# SI5324_CDR_WR_oscillators.net
KiCad netlist of a schematic drawn in Altium Designer
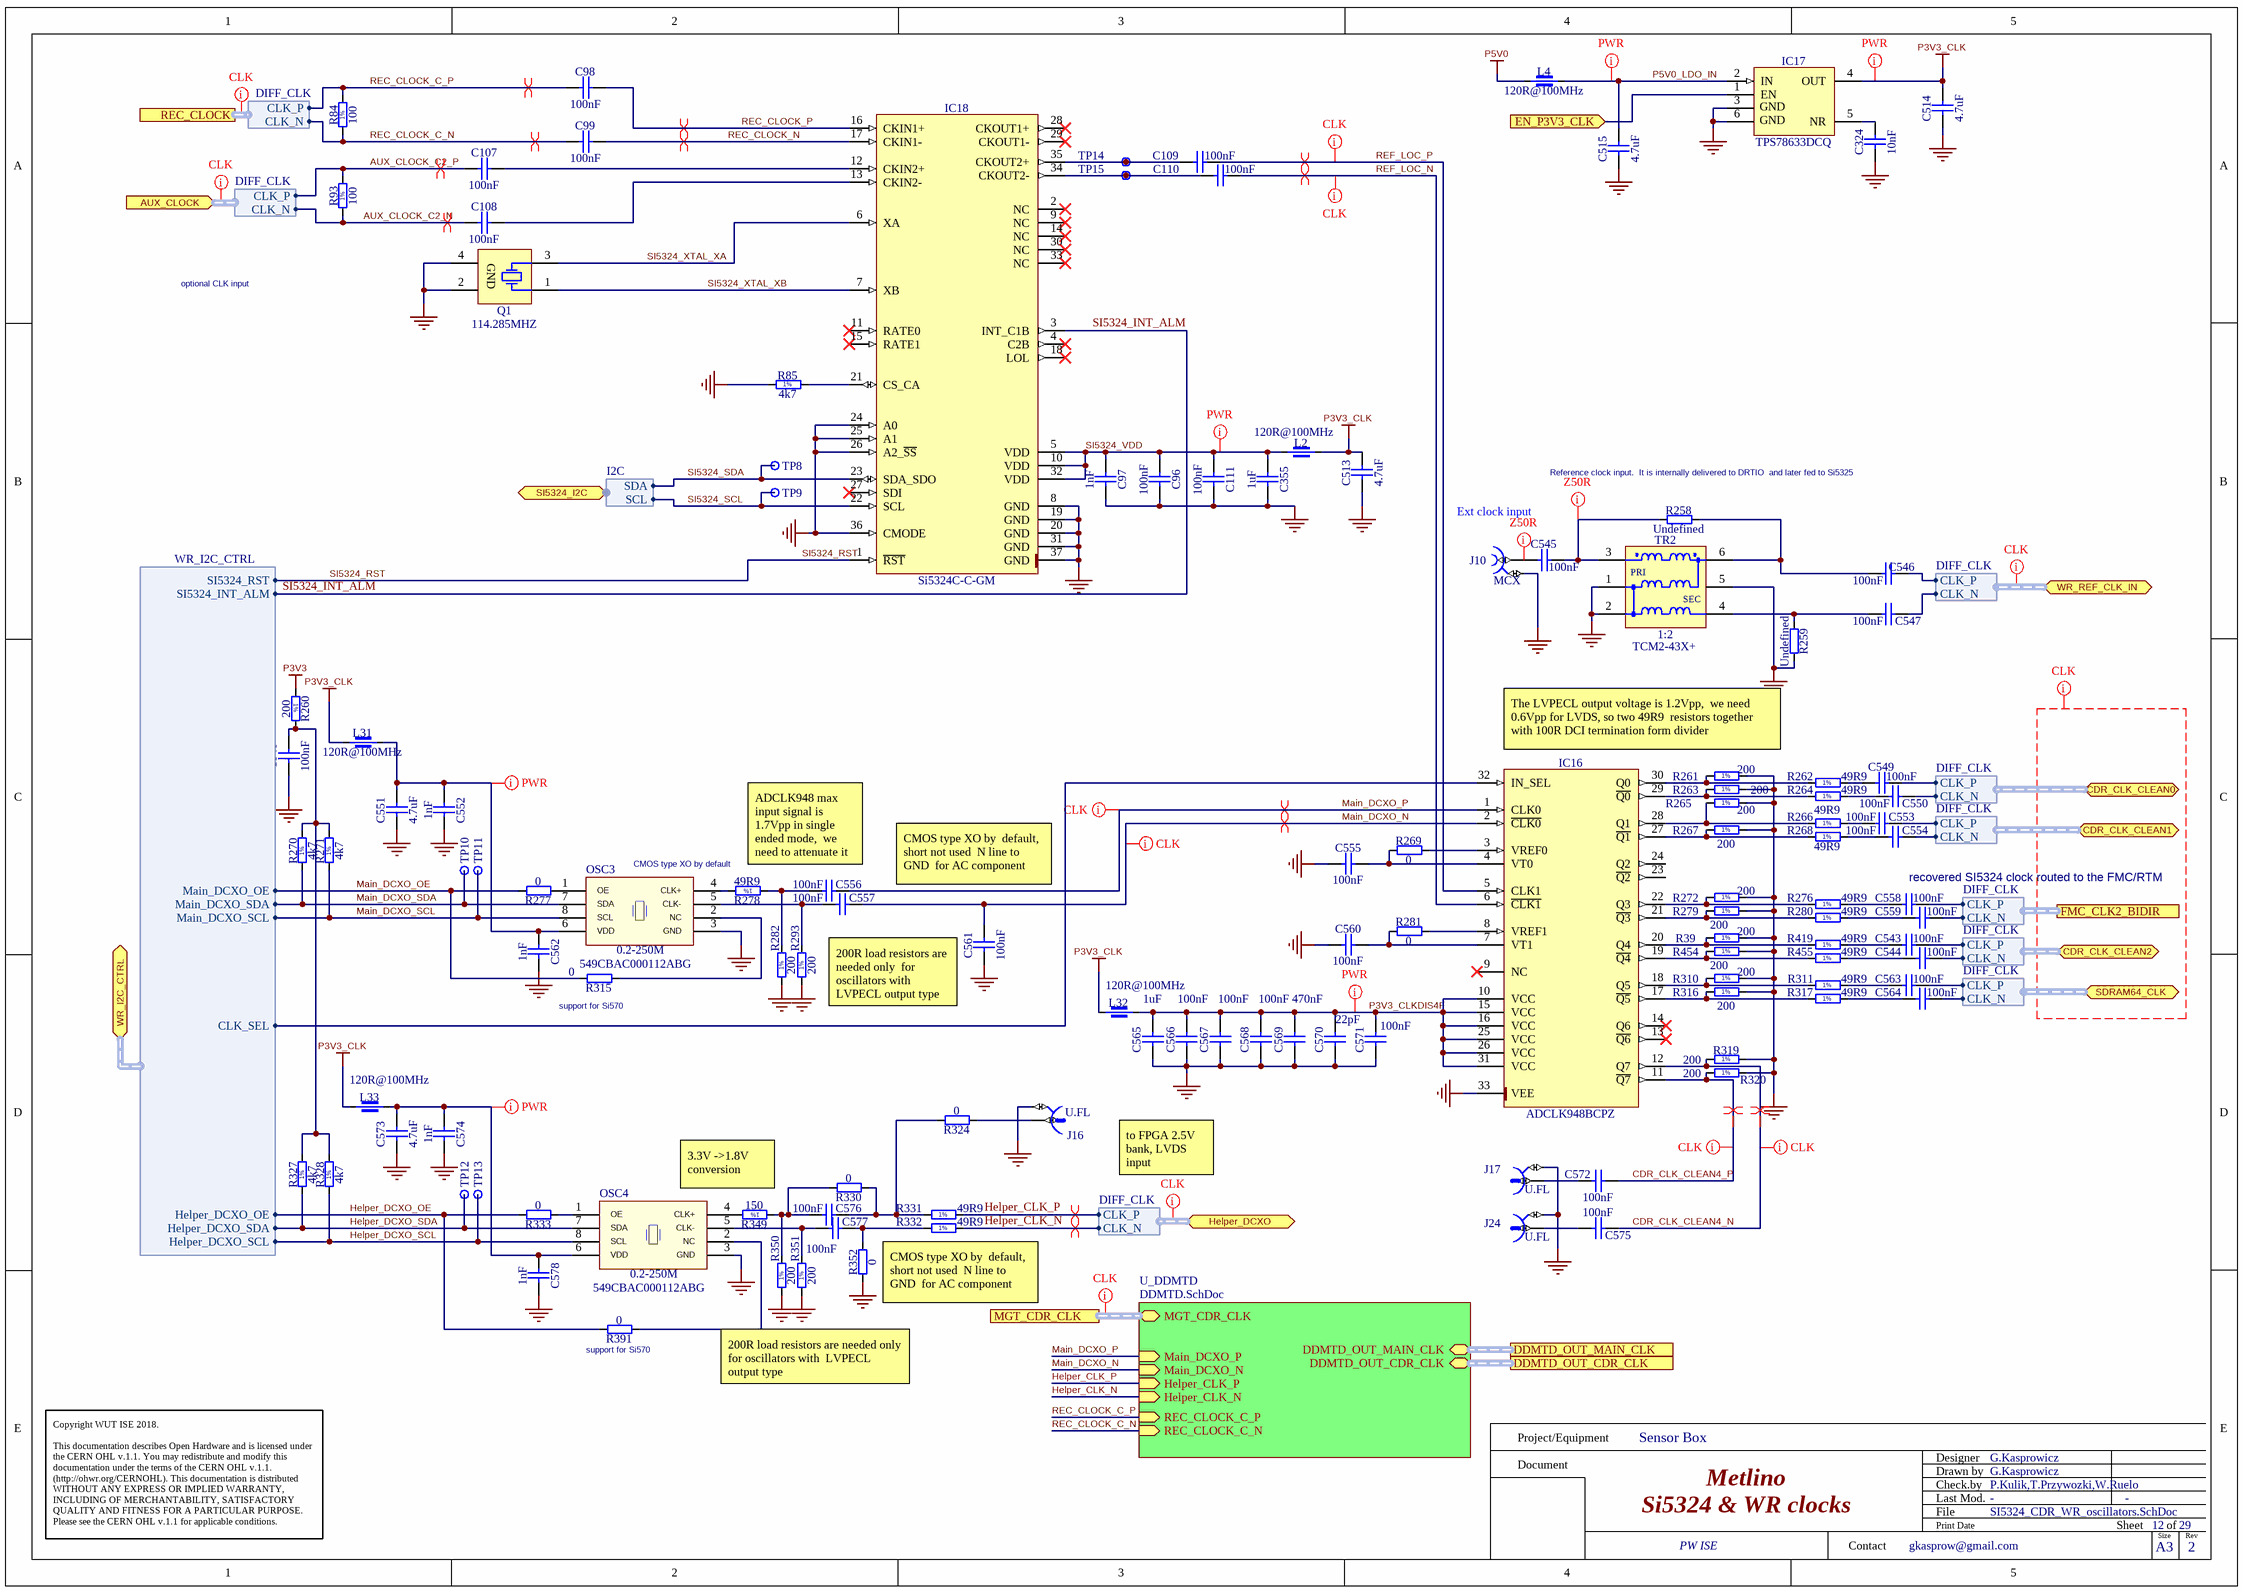
[diagram p0: SI5324_CDR_WR_oscillators.SchDoc]

(export (version "E")
  (design (tool "Eeschema 10.0.6"))
  (components
    (comp (ref "C96")
      (value "100nF")
      (footprint "CAPC0603X33N")
      (description "Non-polarised capacitor")
      (fields
        (field (name "MANUFACTURER PART NUMBER") "CC0201_100NF_6.3V_10%_X5R")
        (field (name "MANUFACTURER") "GENERIC")
        (field (name "AUTHOR") "CERN DEM JLC")
      )
      (libsource (lib "Capacitors") (part "Capacitor - non polarized"))
    )
    (comp (ref "C97")
      (value "1nF")
      (footprint "CAPC0603X33N")
      (description "Non-polarised capacitor")
      (fields
        (field (name "MANUFACTURER PART NUMBER") "CC0201_1NF_16V_10%_X5R")
        (field (name "MANUFACTURER") "GENERIC")
        (field (name "AUTHOR") "CERN DEM JLC")
      )
      (libsource (lib "Capacitors") (part "Capacitor - non polarized"))
    )
    (comp (ref "C98")
      (value "100nF")
      (footprint "CAPC0603X33N")
      (description "Non-polarised capacitor")
      (fields
        (field (name "MANUFACTURER PART NUMBER") "CC0201_100NF_6.3V_10%_X5R")
        (field (name "MANUFACTURER") "GENERIC")
        (field (name "AUTHOR") "CERN DEM JLC")
      )
      (libsource (lib "Capacitors") (part "Capacitor - non polarized"))
    )
    (comp (ref "C99")
      (value "100nF")
      (footprint "CAPC0603X33N")
      (description "Non-polarised capacitor")
      (fields
        (field (name "MANUFACTURER PART NUMBER") "CC0201_100NF_6.3V_10%_X5R")
        (field (name "MANUFACTURER") "GENERIC")
        (field (name "AUTHOR") "CERN DEM JLC")
      )
      (libsource (lib "Capacitors") (part "Capacitor - non polarized"))
    )
    (comp (ref "C107")
      (value "100nF")
      (footprint "CAPC0603X33N")
      (description "Non-polarised capacitor")
      (fields
        (field (name "MANUFACTURER PART NUMBER") "CC0201_100NF_6.3V_10%_X5R")
        (field (name "MANUFACTURER") "GENERIC")
        (field (name "AUTHOR") "CERN DEM JLC")
      )
      (libsource (lib "Capacitors") (part "Capacitor - non polarized"))
    )
    (comp (ref "C108")
      (value "100nF")
      (footprint "CAPC0603X33N")
      (description "Non-polarised capacitor")
      (fields
        (field (name "MANUFACTURER PART NUMBER") "CC0201_100NF_6.3V_10%_X5R")
        (field (name "MANUFACTURER") "GENERIC")
        (field (name "AUTHOR") "CERN DEM JLC")
      )
      (libsource (lib "Capacitors") (part "Capacitor - non polarized"))
    )
    (comp (ref "C109")
      (value "100nF")
      (footprint "CAPC1005X55N")
      (description "Non-polarised capacitor")
      (fields
        (field (name "MANUFACTURER PART NUMBER") "CC0402_100NF_16V_10%_X5R")
        (field (name "MANUFACTURER") "GENERIC")
        (field (name "AUTHOR") "CERN DEM JLC")
      )
      (libsource (lib "Capacitors") (part "Capacitor - non polarized"))
    )
    (comp (ref "C110")
      (value "100nF")
      (footprint "CAPC1005X55N")
      (description "Non-polarised capacitor")
      (fields
        (field (name "MANUFACTURER PART NUMBER") "CC0402_100NF_16V_10%_X5R")
        (field (name "MANUFACTURER") "GENERIC")
        (field (name "AUTHOR") "CERN DEM JLC")
      )
      (libsource (lib "Capacitors") (part "Capacitor - non polarized"))
    )
    (comp (ref "C111")
      (value "100nF")
      (footprint "CAPC0603X33N")
      (description "Non-polarised capacitor")
      (fields
        (field (name "MANUFACTURER PART NUMBER") "CC0201_100NF_6.3V_10%_X5R")
        (field (name "MANUFACTURER") "GENERIC")
        (field (name "AUTHOR") "CERN DEM JLC")
      )
      (libsource (lib "Capacitors") (part "Capacitor - non polarized"))
    )
    (comp (ref "C324")
      (value "10nF")
      (footprint "CAPC1608X87N")
      (description "Non-polarised capacitor")
      (fields
        (field (name "PART NUMBER") "CC0603_10NF_50V_5%_C0G")
        (field (name "VOLTAGE") "50V")
        (field (name "AUTHOR") "CERN DEM JLC")
      )
      (libsource (lib "Capacitors") (part "Capacitor - non polarized"))
    )
    (comp (ref "C355")
      (value "1uF")
      (footprint "CAPC1005X55N")
      (description "Non-polarised capacitor")
      (fields
        (field (name "MANUFACTURER PART NUMBER") "CC0402_1UF_16V_10%_X5R")
        (field (name "MANUFACTURER") "GENERIC")
        (field (name "AUTHOR") "CERN DEM JLC")
      )
      (libsource (lib "Capacitors") (part "Capacitor - non polarized"))
    )
    (comp (ref "C513")
      (value "4.7uF")
      (footprint "CAPC1608X90N")
      (description "Non-polarised capacitor")
      (fields
        (field (name "MANUFACTURER PART NUMBER") "CC0603_4.7UF_25V_10%_X5R")
        (field (name "MANUFACTURER") "GENERIC")
        (field (name "AUTHOR") "CERN DEM JLC")
      )
      (libsource (lib "Capacitors") (part "Capacitor - non polarized"))
    )
    (comp (ref "C514")
      (value "4.7uF")
      (footprint "CAPC1608X90N")
      (description "Non-polarised capacitor")
      (fields
        (field (name "MANUFACTURER PART NUMBER") "CC0603_4.7UF_25V_10%_X5R")
        (field (name "MANUFACTURER") "GENERIC")
        (field (name "AUTHOR") "CERN DEM JLC")
      )
      (libsource (lib "Capacitors") (part "Capacitor - non polarized"))
    )
    (comp (ref "C515")
      (value "4.7uF")
      (footprint "CAPC1608X90N")
      (description "Non-polarised capacitor")
      (fields
        (field (name "MANUFACTURER PART NUMBER") "CC0603_4.7UF_25V_10%_X5R")
        (field (name "MANUFACTURER") "GENERIC")
        (field (name "AUTHOR") "CERN DEM JLC")
      )
      (libsource (lib "Capacitors") (part "Capacitor - non polarized"))
    )
    (comp (ref "C543")
      (value "100nF")
      (footprint "CAPC0603X33N")
      (description "Non-polarised capacitor")
      (fields
        (field (name "MANUFACTURER PART NUMBER") "CC0201_100NF_6.3V_10%_X5R")
        (field (name "MANUFACTURER") "GENERIC")
        (field (name "AUTHOR") "CERN DEM JLC")
      )
      (libsource (lib "Capacitors") (part "Capacitor - non polarized"))
    )
    (comp (ref "C544")
      (value "100nF")
      (footprint "CAPC0603X33N")
      (description "Non-polarised capacitor")
      (fields
        (field (name "MANUFACTURER PART NUMBER") "CC0201_100NF_6.3V_10%_X5R")
        (field (name "MANUFACTURER") "GENERIC")
        (field (name "AUTHOR") "CERN DEM JLC")
      )
      (libsource (lib "Capacitors") (part "Capacitor - non polarized"))
    )
    (comp (ref "C545")
      (value "100nF")
      (footprint "CAPC1005X55N")
      (description "Non-polarised capacitor")
      (fields
        (field (name "MANUFACTURER PART NUMBER") "CC0402_100NF_16V_10%_X5R")
        (field (name "MANUFACTURER") "GENERIC")
        (field (name "AUTHOR") "CERN DEM JLC")
      )
      (libsource (lib "Capacitors") (part "Capacitor - non polarized"))
    )
    (comp (ref "C546")
      (value "100nF")
      (footprint "CAPC1005X55N")
      (description "Non-polarised capacitor")
      (fields
        (field (name "MANUFACTURER PART NUMBER") "CC0402_100NF_16V_10%_X5R")
        (field (name "MANUFACTURER") "GENERIC")
        (field (name "AUTHOR") "CERN DEM JLC")
      )
      (libsource (lib "Capacitors") (part "Capacitor - non polarized"))
    )
    (comp (ref "C547")
      (value "100nF")
      (footprint "CAPC1005X55N")
      (description "Non-polarised capacitor")
      (fields
        (field (name "MANUFACTURER PART NUMBER") "CC0402_100NF_16V_10%_X5R")
        (field (name "MANUFACTURER") "GENERIC")
        (field (name "AUTHOR") "CERN DEM JLC")
      )
      (libsource (lib "Capacitors") (part "Capacitor - non polarized"))
    )
    (comp (ref "C548")
      (value "100nF")
      (footprint "CAPC0603X33N")
      (description "Non-polarised capacitor")
      (fields
        (field (name "MANUFACTURER PART NUMBER") "CC0201_100NF_6.3V_10%_X5R")
        (field (name "MANUFACTURER") "GENERIC")
        (field (name "AUTHOR") "CERN DEM JLC")
      )
      (libsource (lib "Capacitors") (part "Capacitor - non polarized"))
    )
    (comp (ref "C549")
      (value "100nF")
      (footprint "CAPC0603X33N")
      (description "Non-polarised capacitor")
      (fields
        (field (name "MANUFACTURER PART NUMBER") "CC0201_100NF_6.3V_10%_X5R")
        (field (name "MANUFACTURER") "GENERIC")
        (field (name "AUTHOR") "CERN DEM JLC")
      )
      (libsource (lib "Capacitors") (part "Capacitor - non polarized"))
    )
    (comp (ref "C550")
      (value "100nF")
      (footprint "CAPC0603X33N")
      (description "Non-polarised capacitor")
      (fields
        (field (name "MANUFACTURER PART NUMBER") "CC0201_100NF_6.3V_10%_X5R")
        (field (name "MANUFACTURER") "GENERIC")
        (field (name "AUTHOR") "CERN DEM JLC")
      )
      (libsource (lib "Capacitors") (part "Capacitor - non polarized"))
    )
    (comp (ref "C551")
      (value "4.7uF")
      (footprint "CAPC1608X90N")
      (description "Non-polarised capacitor")
      (fields
        (field (name "MANUFACTURER PART NUMBER") "CC0603_4.7UF_25V_10%_X5R")
        (field (name "MANUFACTURER") "GENERIC")
        (field (name "AUTHOR") "CERN DEM JLC")
      )
      (libsource (lib "Capacitors") (part "Capacitor - non polarized"))
    )
    (comp (ref "C552")
      (value "1nF")
      (footprint "CAPC0603X33N")
      (description "Non-polarised capacitor")
      (fields
        (field (name "MANUFACTURER PART NUMBER") "CC0201_1NF_16V_10%_X5R")
        (field (name "MANUFACTURER") "GENERIC")
        (field (name "AUTHOR") "CERN DEM JLC")
      )
      (libsource (lib "Capacitors") (part "Capacitor - non polarized"))
    )
    (comp (ref "C553")
      (value "100nF")
      (footprint "CAPC0603X33N")
      (description "Non-polarised capacitor")
      (fields
        (field (name "MANUFACTURER PART NUMBER") "CC0201_100NF_6.3V_10%_X5R")
        (field (name "MANUFACTURER") "GENERIC")
        (field (name "AUTHOR") "CERN DEM JLC")
      )
      (libsource (lib "Capacitors") (part "Capacitor - non polarized"))
    )
    (comp (ref "C554")
      (value "100nF")
      (footprint "CAPC0603X33N")
      (description "Non-polarised capacitor")
      (fields
        (field (name "MANUFACTURER PART NUMBER") "CC0201_100NF_6.3V_10%_X5R")
        (field (name "MANUFACTURER") "GENERIC")
        (field (name "AUTHOR") "CERN DEM JLC")
      )
      (libsource (lib "Capacitors") (part "Capacitor - non polarized"))
    )
    (comp (ref "C555")
      (value "100nF")
      (footprint "CAPC0603X33N")
      (description "Non-polarised capacitor")
      (fields
        (field (name "MANUFACTURER PART NUMBER") "CC0201_100NF_6.3V_10%_X5R")
        (field (name "MANUFACTURER") "GENERIC")
        (field (name "AUTHOR") "CERN DEM JLC")
      )
      (libsource (lib "Capacitors") (part "Capacitor - non polarized"))
    )
    (comp (ref "C556")
      (value "100nF")
      (footprint "CAPC1005X55N")
      (description "Non-polarised capacitor")
      (fields
        (field (name "MANUFACTURER PART NUMBER") "CC0402_100NF_16V_10%_X5R")
        (field (name "MANUFACTURER") "GENERIC")
        (field (name "AUTHOR") "CERN DEM JLC")
      )
      (libsource (lib "Capacitors") (part "Capacitor - non polarized"))
    )
    (comp (ref "C557")
      (value "100nF")
      (footprint "CAPC1005X55N")
      (description "Non-polarised capacitor")
      (fields
        (field (name "MANUFACTURER PART NUMBER") "CC0402_100NF_16V_10%_X5R")
        (field (name "MANUFACTURER") "GENERIC")
        (field (name "AUTHOR") "CERN DEM JLC")
      )
      (libsource (lib "Capacitors") (part "Capacitor - non polarized"))
    )
    (comp (ref "C558")
      (value "100nF")
      (footprint "CAPC0603X33N")
      (description "Non-polarised capacitor")
      (fields
        (field (name "MANUFACTURER PART NUMBER") "CC0201_100NF_6.3V_10%_X5R")
        (field (name "MANUFACTURER") "GENERIC")
        (field (name "AUTHOR") "CERN DEM JLC")
      )
      (libsource (lib "Capacitors") (part "Capacitor - non polarized"))
    )
    (comp (ref "C559")
      (value "100nF")
      (footprint "CAPC0603X33N")
      (description "Non-polarised capacitor")
      (fields
        (field (name "MANUFACTURER PART NUMBER") "CC0201_100NF_6.3V_10%_X5R")
        (field (name "MANUFACTURER") "GENERIC")
        (field (name "AUTHOR") "CERN DEM JLC")
      )
      (libsource (lib "Capacitors") (part "Capacitor - non polarized"))
    )
    (comp (ref "C560")
      (value "100nF")
      (footprint "CAPC0603X33N")
      (description "Non-polarised capacitor")
      (fields
        (field (name "MANUFACTURER PART NUMBER") "CC0201_100NF_6.3V_10%_X5R")
        (field (name "MANUFACTURER") "GENERIC")
        (field (name "AUTHOR") "CERN DEM JLC")
      )
      (libsource (lib "Capacitors") (part "Capacitor - non polarized"))
    )
    (comp (ref "C561")
      (value "100nF")
      (footprint "CAPC0603X33N")
      (description "Non-polarised capacitor")
      (fields
        (field (name "MANUFACTURER PART NUMBER") "CC0201_100NF_6.3V_10%_X5R")
        (field (name "MANUFACTURER") "GENERIC")
        (field (name "AUTHOR") "CERN DEM JLC")
      )
      (libsource (lib "Capacitors") (part "Capacitor - non polarized"))
    )
    (comp (ref "C562")
      (value "1nF")
      (footprint "CAPC0603X33N")
      (description "Non-polarised capacitor")
      (fields
        (field (name "MANUFACTURER PART NUMBER") "CC0201_1NF_16V_10%_X5R")
        (field (name "MANUFACTURER") "GENERIC")
        (field (name "AUTHOR") "CERN DEM JLC")
      )
      (libsource (lib "Capacitors") (part "Capacitor - non polarized"))
    )
    (comp (ref "C563")
      (value "100nF")
      (footprint "CAPC0603X33N")
      (description "Non-polarised capacitor")
      (fields
        (field (name "MANUFACTURER PART NUMBER") "CC0201_100NF_6.3V_10%_X5R")
        (field (name "MANUFACTURER") "GENERIC")
        (field (name "AUTHOR") "CERN DEM JLC")
      )
      (libsource (lib "Capacitors") (part "Capacitor - non polarized"))
    )
    (comp (ref "C564")
      (value "100nF")
      (footprint "CAPC0603X33N")
      (description "Non-polarised capacitor")
      (fields
        (field (name "MANUFACTURER PART NUMBER") "CC0201_100NF_6.3V_10%_X5R")
        (field (name "MANUFACTURER") "GENERIC")
        (field (name "AUTHOR") "CERN DEM JLC")
      )
      (libsource (lib "Capacitors") (part "Capacitor - non polarized"))
    )
    (comp (ref "C565")
      (value "1uF")
      (footprint "CAPC1005X55N")
      (description "Non-polarised capacitor")
      (fields
        (field (name "MANUFACTURER PART NUMBER") "CC0402_1UF_16V_10%_X5R")
        (field (name "MANUFACTURER") "GENERIC")
        (field (name "AUTHOR") "CERN DEM JLC")
      )
      (libsource (lib "Capacitors") (part "Capacitor - non polarized"))
    )
    (comp (ref "C566")
      (value "100nF")
      (footprint "CAPC0603X33N")
      (description "Non-polarised capacitor")
      (fields
        (field (name "MANUFACTURER PART NUMBER") "CC0201_100NF_6.3V_10%_X5R")
        (field (name "MANUFACTURER") "GENERIC")
        (field (name "AUTHOR") "CERN DEM JLC")
      )
      (libsource (lib "Capacitors") (part "Capacitor - non polarized"))
    )
    (comp (ref "C567")
      (value "100nF")
      (footprint "CAPC0603X33N")
      (description "Non-polarised capacitor")
      (fields
        (field (name "MANUFACTURER PART NUMBER") "CC0201_100NF_6.3V_10%_X5R")
        (field (name "MANUFACTURER") "GENERIC")
        (field (name "AUTHOR") "CERN DEM JLC")
      )
      (libsource (lib "Capacitors") (part "Capacitor - non polarized"))
    )
    (comp (ref "C568")
      (value "100nF")
      (footprint "CAPC0603X33N")
      (description "Non-polarised capacitor")
      (fields
        (field (name "MANUFACTURER PART NUMBER") "CC0201_100NF_6.3V_10%_X5R")
        (field (name "MANUFACTURER") "GENERIC")
        (field (name "AUTHOR") "CERN DEM JLC")
      )
      (libsource (lib "Capacitors") (part "Capacitor - non polarized"))
    )
    (comp (ref "C569")
      (value "470nF")
      (footprint "CAPC1005X55N")
      (description "Non-polarised capacitor")
      (fields
        (field (name "MANUFACTURER PART NUMBER") "CC0402_470NF_16V_10%_X5R")
        (field (name "MANUFACTURER") "GENERIC")
        (field (name "AUTHOR") "CERN DEM JLC")
      )
      (libsource (lib "Capacitors") (part "Capacitor - non polarized"))
    )
    (comp (ref "C570")
      (value "22pF")
      (footprint "CAPC1005X55N")
      (description "Non-polarised capacitor")
      (fields
        (field (name "MANUFACTURER PART NUMBER") "CC0402_22PF_50V_5%_C0G")
        (field (name "MANUFACTURER") "GENERIC")
        (field (name "AUTHOR") "CERN DEM JLC")
      )
      (libsource (lib "Capacitors") (part "Capacitor - non polarized"))
    )
    (comp (ref "C571")
      (value "100nF")
      (footprint "CAPC0603X33N")
      (description "Non-polarised capacitor")
      (fields
        (field (name "MANUFACTURER PART NUMBER") "CC0201_100NF_6.3V_10%_X5R")
        (field (name "MANUFACTURER") "GENERIC")
        (field (name "AUTHOR") "CERN DEM JLC")
      )
      (libsource (lib "Capacitors") (part "Capacitor - non polarized"))
    )
    (comp (ref "C572")
      (value "100nF")
      (footprint "CAPC0603X33N")
      (description "Non-polarised capacitor")
      (fields
        (field (name "MANUFACTURER PART NUMBER") "CC0201_100NF_6.3V_10%_X5R")
        (field (name "MANUFACTURER") "GENERIC")
        (field (name "AUTHOR") "CERN DEM JLC")
      )
      (libsource (lib "Capacitors") (part "Capacitor - non polarized"))
    )
    (comp (ref "C573")
      (value "4.7uF")
      (footprint "CAPC1608X90N")
      (description "Non-polarised capacitor")
      (fields
        (field (name "MANUFACTURER PART NUMBER") "CC0603_4.7UF_25V_10%_X5R")
        (field (name "MANUFACTURER") "GENERIC")
        (field (name "AUTHOR") "CERN DEM JLC")
      )
      (libsource (lib "Capacitors") (part "Capacitor - non polarized"))
    )
    (comp (ref "C574")
      (value "1nF")
      (footprint "CAPC0603X33N")
      (description "Non-polarised capacitor")
      (fields
        (field (name "MANUFACTURER PART NUMBER") "CC0201_1NF_16V_10%_X5R")
        (field (name "MANUFACTURER") "GENERIC")
        (field (name "AUTHOR") "CERN DEM JLC")
      )
      (libsource (lib "Capacitors") (part "Capacitor - non polarized"))
    )
    (comp (ref "C575")
      (value "100nF")
      (footprint "CAPC0603X33N")
      (description "Non-polarised capacitor")
      (fields
        (field (name "MANUFACTURER PART NUMBER") "CC0201_100NF_6.3V_10%_X5R")
        (field (name "MANUFACTURER") "GENERIC")
        (field (name "AUTHOR") "CERN DEM JLC")
      )
      (libsource (lib "Capacitors") (part "Capacitor - non polarized"))
    )
    (comp (ref "C576")
      (value "100nF")
      (footprint "CAPC1005X55N")
      (description "Non-polarised capacitor")
      (fields
        (field (name "MANUFACTURER PART NUMBER") "CC0402_100NF_16V_10%_X5R")
        (field (name "MANUFACTURER") "GENERIC")
        (field (name "AUTHOR") "CERN DEM JLC")
      )
      (libsource (lib "Capacitors") (part "Capacitor - non polarized"))
    )
    (comp (ref "C577")
      (value "100nF")
      (footprint "CAPC1005X55N")
      (description "Non-polarised capacitor")
      (fields
        (field (name "MANUFACTURER PART NUMBER") "CC0402_100NF_16V_10%_X5R")
        (field (name "MANUFACTURER") "GENERIC")
        (field (name "AUTHOR") "CERN DEM JLC")
      )
      (libsource (lib "Capacitors") (part "Capacitor - non polarized"))
    )
    (comp (ref "C578")
      (value "1nF")
      (footprint "CAPC0603X33N")
      (description "Non-polarised capacitor")
      (fields
        (field (name "MANUFACTURER PART NUMBER") "CC0201_1NF_16V_10%_X5R")
        (field (name "MANUFACTURER") "GENERIC")
        (field (name "AUTHOR") "CERN DEM JLC")
      )
      (libsource (lib "Capacitors") (part "Capacitor - non polarized"))
    )
    (comp (ref "IC16")
      (value "ADCLK948BCPZ")
      (footprint "QFN50P500X500X80-33N-S285")
      (description "Two Selectable Inputs, 8 LVPECL Outputs, SiGe Clock Fanout Buffer")
      (fields (field (name "MANUFACTURER") "ANALOG DEVICES") (field (name "AUTHOR") "CERN DEM MR"))
      (libsource (lib "ICs And Semiconductors") (part "ADCLK948"))
    )
    (comp (ref "IC17")
      (value "TPS78633DCQ")
      (footprint "SOT127P700X180-6N")
      (description "Ultralow-Noise, High-PSRR, Fast, RF, 1.5A Low-Dropout Linear Regulator")
      (fields (field (name "MANUFACTURER") "TEXAS INSTRUMENTS") (field (name "AUTHOR") "CERN DEM JMW"))
      (libsource (lib "ICs And Semiconductors") (part "TPS786xxDCQ"))
    )
    (comp (ref "IC18")
      (value "Si5324C-C-GM")
      (footprint "QFN50P600X600X90-37N-S425")
      (description "Any Frequency Precision Clock Multiplier/Jitter Attenuator")
      (fields (field (name "MANUFACTURER") "SILICON LABS") (field (name "AUTHOR") "CERN DEM JLC"))
      (libsource (lib "ICs And Semiconductors") (part "Si5324"))
    )
    (comp (ref "J10")
      (value "MCX")
      (footprint "AMPHENOL_ARF2521-ND")
      (fields
        (field (name "PART NUMBER") "AMPHENOL_ARF2521-ND")
        (field (name "MANUFACTURER") "AMPHENOL")
        (field (name "AUTHOR") "GK")
      )
      (libsource (lib "LIBRARY_SCH") (part "CON_MCX"))
    )
    (comp (ref "J16")
      (value "U.FL")
      (footprint "HIROSE_U.FL-R-SMT-1(10)")
      (fields
        (field (name "MANUFACTURER PART NUMBER") "U.FL-R-SMT-1(10)")
        (field (name "MANUFACTURER") "HIROSE (HRS)")
        (field (name "PART NUMBER") "HIROSE_U.FL-R-SMT-1(10)")
        (field (name "AUTHOR") "CERN DEM JLC")
      )
      (libsource (lib "Connectors") (part "Coax_1Male_1Shield"))
    )
    (comp (ref "J17")
      (value "U.FL")
      (footprint "HIROSE_U.FL-R-SMT-1(10)")
      (fields
        (field (name "MANUFACTURER PART NUMBER") "U.FL-R-SMT-1(10)")
        (field (name "MANUFACTURER") "HIROSE (HRS)")
        (field (name "PART NUMBER") "HIROSE_U.FL-R-SMT-1(10)")
        (field (name "AUTHOR") "CERN DEM JLC")
      )
      (libsource (lib "") (part "Coax_1Male_1Shield_1"))
    )
    (comp (ref "J24")
      (value "U.FL")
      (footprint "HIROSE_U.FL-R-SMT-1(10)")
      (fields
        (field (name "MANUFACTURER PART NUMBER") "U.FL-R-SMT-1(10)")
        (field (name "MANUFACTURER") "HIROSE (HRS)")
        (field (name "PART NUMBER") "HIROSE_U.FL-R-SMT-1(10)")
        (field (name "AUTHOR") "CERN DEM JLC")
      )
      (libsource (lib "") (part "Coax_1Male_1Shield_1"))
    )
    (comp (ref "L2")
      (value "120R@100MHz")
      (footprint "INDC1608X95N")
      (fields
        (field (name "MANUFACTURER PART NUMBER") "BLM18PG121SN1D")
        (field (name "MANUFACTURER") "MURATA")
        (field (name "PART NUMBER") "IND0603_MURATA_BLM18PG121SN1D")
        (field (name "AUTHOR") "CERN DEM BC")
      )
      (libsource (lib "Inductors & Transformers") (part "Ferrite Bead"))
    )
    (comp (ref "L4")
      (value "120R@100MHz")
      (footprint "INDC1608X95N")
      (fields
        (field (name "MANUFACTURER PART NUMBER") "BLM18PG121SN1D")
        (field (name "MANUFACTURER") "MURATA")
        (field (name "PART NUMBER") "IND0603_MURATA_BLM18PG121SN1D")
        (field (name "AUTHOR") "CERN DEM BC")
      )
      (libsource (lib "") (part "Ferrite Bead_1"))
    )
    (comp (ref "L31")
      (value "120R@100MHz")
      (footprint "INDC1608X95N")
      (fields
        (field (name "MANUFACTURER PART NUMBER") "BLM18PG121SN1D")
        (field (name "MANUFACTURER") "MURATA")
        (field (name "PART NUMBER") "IND0603_MURATA_BLM18PG121SN1D")
        (field (name "AUTHOR") "CERN DEM BC")
      )
      (libsource (lib "") (part "Ferrite Bead_1"))
    )
    (comp (ref "L32")
      (value "120R@100MHz")
      (footprint "INDC1608X95N")
      (fields
        (field (name "MANUFACTURER PART NUMBER") "BLM18PG121SN1D")
        (field (name "MANUFACTURER") "MURATA")
        (field (name "PART NUMBER") "IND0603_MURATA_BLM18PG121SN1D")
        (field (name "AUTHOR") "CERN DEM BC")
      )
      (libsource (lib "") (part "Ferrite Bead_1"))
    )
    (comp (ref "L33")
      (value "120R@100MHz")
      (footprint "INDC1608X95N")
      (fields
        (field (name "MANUFACTURER PART NUMBER") "BLM18PG121SN1D")
        (field (name "MANUFACTURER") "MURATA")
        (field (name "PART NUMBER") "IND0603_MURATA_BLM18PG121SN1D")
        (field (name "AUTHOR") "CERN DEM BC")
      )
      (libsource (lib "") (part "Ferrite Bead_1"))
    )
    (comp (ref "OSC3")
      (value "0.2-250M")
      (footprint "OSC_SILICON-LAB_SI549")
      (fields
        (field (name "MANUFACTURER PART NUMBER") "549CBAC000112ABG")
        (field (name "MANUFACTURER") "Silabs")
        (field (name "PART NUMBER") "OSC_0.2_250M_SILICON-LAB_549CBAC000112ABG")
      )
      (libsource (lib "LIBRARY_SCH") (part "OSC_SILICON-LAB_SI549"))
    )
    (comp (ref "OSC4")
      (value "0.2-250M")
      (footprint "OSC_SILICON-LAB_SI549")
      (fields
        (field (name "MANUFACTURER PART NUMBER") "549CBAC000112ABG")
        (field (name "MANUFACTURER") "Silabs")
        (field (name "PART NUMBER") "OSC_0.2_250M_SILICON-LAB_549CBAC000112ABG")
      )
      (libsource (lib "LIBRARY_SCH") (part "OSC_SILICON-LAB_SI549"))
    )
    (comp (ref "Q1")
      (value "114.285MHZ")
      (footprint "XTAL_CONNOR_CS")
      (description "Crystal 4 pins 1=XTAL Control 2=GND3=XTAL 4=GND")
      (fields
        (field (name "MANUFACTURER PART NUMBER") "CS-023-114.285M")
        (field (name "MANUFACTURER") "CONNOR-WINFIELD")
        (field (name "AUTHOR") "CERN DEM JLC")
      )
      (libsource (lib "ICs And Semiconductors") (part "Quartz Crystal 1X 2GND 3X 4GND"))
    )
    (comp (ref "R39")
      (value "200")
      (footprint "RESC1005X40N")
      (description "Resistor - 1%")
      (fields
        (field (name "MANUFACTURER PART NUMBER") "R0402_200R_1%_0.0625W_100PPM")
        (field (name "MANUFACTURER") "GENERIC")
        (field (name "AUTHOR") "CERN DEM JLC")
      )
      (libsource (lib "Resistors") (part "Resistor - 1%"))
    )
    (comp (ref "R84")
      (value "100")
      (footprint "RESC1005X40N")
      (description "Resistor - 1%")
      (fields
        (field (name "MANUFACTURER PART NUMBER") "R0402_100R_1%_0.0625W_100PPM")
        (field (name "MANUFACTURER") "GENERIC")
        (field (name "AUTHOR") "CERN DEM JLC")
      )
      (libsource (lib "Resistors") (part "Resistor - 1%"))
    )
    (comp (ref "R85")
      (value "4k7")
      (footprint "RESC1005X40N")
      (description "Resistor - 1%")
      (fields
        (field (name "MANUFACTURER PART NUMBER") "R0402_4K7_1%_0.0625W_100PPM")
        (field (name "MANUFACTURER") "GENERIC")
        (field (name "AUTHOR") "CERN DEM JLC")
      )
      (libsource (lib "Resistors") (part "Resistor - 1%"))
    )
    (comp (ref "R93")
      (value "100")
      (footprint "RESC1005X40N")
      (description "Resistor - 1%")
      (fields
        (field (name "MANUFACTURER PART NUMBER") "R0402_100R_1%_0.0625W_100PPM")
        (field (name "MANUFACTURER") "GENERIC")
        (field (name "AUTHOR") "CERN DEM JLC")
      )
      (libsource (lib "Resistors") (part "Resistor - 1%"))
    )
    (comp (ref "R258")
      (value "Undefined")
      (footprint "RESC1005X40N")
      (description "Resistor")
      (fields
        (field (name "MANUFACTURER PART NUMBER") "R0402_NO-VALUE")
        (field (name "AUTHOR") "CERN DEM JLC")
      )
      (libsource (lib "Resistors") (part "Resistor"))
    )
    (comp (ref "R259")
      (value "Undefined")
      (footprint "RESC1005X40N")
      (description "Resistor")
      (fields
        (field (name "MANUFACTURER PART NUMBER") "R0402_NO-VALUE")
        (field (name "AUTHOR") "CERN DEM JLC")
      )
      (libsource (lib "Resistors") (part "Resistor"))
    )
    (comp (ref "R260")
      (value "200")
      (footprint "RESC1005X40N")
      (description "Resistor - 1%")
      (fields
        (field (name "MANUFACTURER PART NUMBER") "R0402_200R_1%_0.0625W_100PPM")
        (field (name "MANUFACTURER") "GENERIC")
        (field (name "AUTHOR") "CERN DEM JLC")
      )
      (libsource (lib "Resistors") (part "Resistor - 1%"))
    )
    (comp (ref "R261")
      (value "200")
      (footprint "RESC1005X40N")
      (description "Resistor - 1%")
      (fields
        (field (name "MANUFACTURER PART NUMBER") "R0402_200R_1%_0.0625W_100PPM")
        (field (name "MANUFACTURER") "GENERIC")
        (field (name "AUTHOR") "CERN DEM JLC")
      )
      (libsource (lib "Resistors") (part "Resistor - 1%"))
    )
    (comp (ref "R262")
      (value "49R9")
      (footprint "RESC1005X40N")
      (description "Resistor - 1%")
      (fields
        (field (name "MANUFACTURER PART NUMBER") "R0402_49R9_1%_0.0625W_100PPM")
        (field (name "MANUFACTURER") "GENERIC")
        (field (name "AUTHOR") "CERN DEM JLC")
      )
      (libsource (lib "Resistors") (part "Resistor - 1%"))
    )
    (comp (ref "R263")
      (value "200")
      (footprint "RESC1005X40N")
      (description "Resistor - 1%")
      (fields
        (field (name "MANUFACTURER PART NUMBER") "R0402_200R_1%_0.0625W_100PPM")
        (field (name "MANUFACTURER") "GENERIC")
        (field (name "AUTHOR") "CERN DEM JLC")
      )
      (libsource (lib "Resistors") (part "Resistor - 1%"))
    )
    (comp (ref "R264")
      (value "49R9")
      (footprint "RESC1005X40N")
      (description "Resistor - 1%")
      (fields
        (field (name "MANUFACTURER PART NUMBER") "R0402_49R9_1%_0.0625W_100PPM")
        (field (name "MANUFACTURER") "GENERIC")
        (field (name "AUTHOR") "CERN DEM JLC")
      )
      (libsource (lib "Resistors") (part "Resistor - 1%"))
    )
    (comp (ref "R265")
      (value "200")
      (footprint "RESC1005X40N")
      (description "Resistor - 1%")
      (fields
        (field (name "MANUFACTURER PART NUMBER") "R0402_200R_1%_0.0625W_100PPM")
        (field (name "MANUFACTURER") "GENERIC")
        (field (name "AUTHOR") "CERN DEM JLC")
      )
      (libsource (lib "Resistors") (part "Resistor - 1%"))
    )
    (comp (ref "R266")
      (value "49R9")
      (footprint "RESC1005X40N")
      (description "Resistor - 1%")
      (fields
        (field (name "MANUFACTURER PART NUMBER") "R0402_49R9_1%_0.0625W_100PPM")
        (field (name "MANUFACTURER") "GENERIC")
        (field (name "AUTHOR") "CERN DEM JLC")
      )
      (libsource (lib "Resistors") (part "Resistor - 1%"))
    )
    (comp (ref "R267")
      (value "200")
      (footprint "RESC1005X40N")
      (description "Resistor - 1%")
      (fields
        (field (name "MANUFACTURER PART NUMBER") "R0402_200R_1%_0.0625W_100PPM")
        (field (name "MANUFACTURER") "GENERIC")
        (field (name "AUTHOR") "CERN DEM JLC")
      )
      (libsource (lib "Resistors") (part "Resistor - 1%"))
    )
    (comp (ref "R268")
      (value "49R9")
      (footprint "RESC1005X40N")
      (description "Resistor - 1%")
      (fields
        (field (name "MANUFACTURER PART NUMBER") "R0402_49R9_1%_0.0625W_100PPM")
        (field (name "MANUFACTURER") "GENERIC")
        (field (name "AUTHOR") "CERN DEM JLC")
      )
      (libsource (lib "Resistors") (part "Resistor - 1%"))
    )
    (comp (ref "R269")
      (value "0")
      (footprint "RESC1005X40N")
      (description "Resistor")
      (fields
        (field (name "MANUFACTURER PART NUMBER") "R0402_0R_JUMPER")
        (field (name "MANUFACTURER") "GENERIC")
        (field (name "AUTHOR") "CERN DEM JLC")
      )
      (libsource (lib "Resistors") (part "Resistor"))
    )
    (comp (ref "R270")
      (value "4k7")
      (footprint "RESC1005X40N")
      (description "Resistor - 1%")
      (fields
        (field (name "MANUFACTURER PART NUMBER") "R0402_4K7_1%_0.0625W_100PPM")
        (field (name "MANUFACTURER") "GENERIC")
        (field (name "AUTHOR") "CERN DEM JLC")
      )
      (libsource (lib "Resistors") (part "Resistor - 1%"))
    )
    (comp (ref "R271")
      (value "4k7")
      (footprint "RESC1005X40N")
      (description "Resistor - 1%")
      (fields
        (field (name "MANUFACTURER PART NUMBER") "R0402_4K7_1%_0.0625W_100PPM")
        (field (name "MANUFACTURER") "GENERIC")
        (field (name "AUTHOR") "CERN DEM JLC")
      )
      (libsource (lib "Resistors") (part "Resistor - 1%"))
    )
    (comp (ref "R272")
      (value "200")
      (footprint "RESC1005X40N")
      (description "Resistor - 1%")
      (fields
        (field (name "MANUFACTURER PART NUMBER") "R0402_200R_1%_0.0625W_100PPM")
        (field (name "MANUFACTURER") "GENERIC")
        (field (name "AUTHOR") "CERN DEM JLC")
      )
      (libsource (lib "Resistors") (part "Resistor - 1%"))
    )
    (comp (ref "R276")
      (value "49R9")
      (footprint "RESC1005X40N")
      (description "Resistor - 1%")
      (fields
        (field (name "MANUFACTURER PART NUMBER") "R0402_49R9_1%_0.0625W_100PPM")
        (field (name "MANUFACTURER") "GENERIC")
        (field (name "AUTHOR") "CERN DEM JLC")
      )
      (libsource (lib "Resistors") (part "Resistor - 1%"))
    )
    (comp (ref "R277")
      (value "0")
      (footprint "RESC1005X40N")
      (description "Resistor")
      (fields
        (field (name "MANUFACTURER PART NUMBER") "R0402_0R_JUMPER")
        (field (name "MANUFACTURER") "GENERIC")
        (field (name "AUTHOR") "CERN DEM JLC")
      )
      (libsource (lib "Resistors") (part "Resistor"))
    )
    (comp (ref "R278")
      (value "49R9")
      (footprint "RESC1005X40N")
      (description "Resistor - 1%")
      (fields
        (field (name "MANUFACTURER PART NUMBER") "R0402_49R9_1%_0.0625W_100PPM")
        (field (name "MANUFACTURER") "GENERIC")
        (field (name "AUTHOR") "CERN DEM JLC")
      )
      (libsource (lib "Resistors") (part "Resistor - 1%"))
    )
    (comp (ref "R279")
      (value "200")
      (footprint "RESC1005X40N")
      (description "Resistor - 1%")
      (fields
        (field (name "MANUFACTURER PART NUMBER") "R0402_200R_1%_0.0625W_100PPM")
        (field (name "MANUFACTURER") "GENERIC")
        (field (name "AUTHOR") "CERN DEM JLC")
      )
      (libsource (lib "Resistors") (part "Resistor - 1%"))
    )
    (comp (ref "R280")
      (value "49R9")
      (footprint "RESC1005X40N")
      (description "Resistor - 1%")
      (fields
        (field (name "MANUFACTURER PART NUMBER") "R0402_49R9_1%_0.0625W_100PPM")
        (field (name "MANUFACTURER") "GENERIC")
        (field (name "AUTHOR") "CERN DEM JLC")
      )
      (libsource (lib "Resistors") (part "Resistor - 1%"))
    )
    (comp (ref "R281")
      (value "0")
      (footprint "RESC1005X40N")
      (description "Resistor")
      (fields
        (field (name "MANUFACTURER PART NUMBER") "R0402_0R_JUMPER")
        (field (name "MANUFACTURER") "GENERIC")
        (field (name "AUTHOR") "CERN DEM JLC")
      )
      (libsource (lib "Resistors") (part "Resistor"))
    )
    (comp (ref "R282")
      (value "200")
      (footprint "RESC1005X40N")
      (description "Resistor - 1%")
      (fields
        (field (name "MANUFACTURER PART NUMBER") "R0402_200R_1%_0.0625W_100PPM")
        (field (name "MANUFACTURER") "GENERIC")
        (field (name "AUTHOR") "CERN DEM JLC")
      )
      (libsource (lib "Resistors") (part "Resistor - 1%"))
    )
    (comp (ref "R293")
      (value "200")
      (footprint "RESC1005X40N")
      (description "Resistor - 1%")
      (fields
        (field (name "MANUFACTURER PART NUMBER") "R0402_200R_1%_0.0625W_100PPM")
        (field (name "MANUFACTURER") "GENERIC")
        (field (name "AUTHOR") "CERN DEM JLC")
      )
      (libsource (lib "Resistors") (part "Resistor - 1%"))
    )
    (comp (ref "R310")
      (value "200")
      (footprint "RESC1005X40N")
      (description "Resistor - 1%")
      (fields
        (field (name "MANUFACTURER PART NUMBER") "R0402_200R_1%_0.0625W_100PPM")
        (field (name "MANUFACTURER") "GENERIC")
        (field (name "AUTHOR") "CERN DEM JLC")
      )
      (libsource (lib "Resistors") (part "Resistor - 1%"))
    )
    (comp (ref "R311")
      (value "49R9")
      (footprint "RESC1005X40N")
      (description "Resistor - 1%")
      (fields
        (field (name "MANUFACTURER PART NUMBER") "R0402_49R9_1%_0.0625W_100PPM")
        (field (name "MANUFACTURER") "GENERIC")
        (field (name "AUTHOR") "CERN DEM JLC")
      )
      (libsource (lib "Resistors") (part "Resistor - 1%"))
    )
    (comp (ref "R315")
      (value "0")
      (footprint "RESC1005X40N")
      (description "Resistor")
      (fields
        (field (name "MANUFACTURER PART NUMBER") "R0402_0R_JUMPER")
        (field (name "MANUFACTURER") "GENERIC")
        (field (name "AUTHOR") "CERN DEM JLC")
      )
      (libsource (lib "Resistors") (part "Resistor"))
    )
    (comp (ref "R316")
      (value "200")
      (footprint "RESC1005X40N")
      (description "Resistor - 1%")
      (fields
        (field (name "MANUFACTURER PART NUMBER") "R0402_200R_1%_0.0625W_100PPM")
        (field (name "MANUFACTURER") "GENERIC")
        (field (name "AUTHOR") "CERN DEM JLC")
      )
      (libsource (lib "Resistors") (part "Resistor - 1%"))
    )
    (comp (ref "R317")
      (value "49R9")
      (footprint "RESC1005X40N")
      (description "Resistor - 1%")
      (fields
        (field (name "MANUFACTURER PART NUMBER") "R0402_49R9_1%_0.0625W_100PPM")
        (field (name "MANUFACTURER") "GENERIC")
        (field (name "AUTHOR") "CERN DEM JLC")
      )
      (libsource (lib "Resistors") (part "Resistor - 1%"))
    )
    (comp (ref "R319")
      (value "200")
      (footprint "RESC1005X40N")
      (description "Resistor - 1%")
      (fields
        (field (name "MANUFACTURER PART NUMBER") "R0402_200R_1%_0.0625W_100PPM")
        (field (name "MANUFACTURER") "GENERIC")
        (field (name "AUTHOR") "CERN DEM JLC")
      )
      (libsource (lib "Resistors") (part "Resistor - 1%"))
    )
    (comp (ref "R320")
      (value "200")
      (footprint "RESC1005X40N")
      (description "Resistor - 1%")
      (fields
        (field (name "MANUFACTURER PART NUMBER") "R0402_200R_1%_0.0625W_100PPM")
        (field (name "MANUFACTURER") "GENERIC")
        (field (name "AUTHOR") "CERN DEM JLC")
      )
      (libsource (lib "Resistors") (part "Resistor - 1%"))
    )
    (comp (ref "R324")
      (value "0")
      (footprint "RESC1005X40N")
      (description "Resistor")
      (fields
        (field (name "MANUFACTURER PART NUMBER") "R0402_0R_JUMPER")
        (field (name "MANUFACTURER") "GENERIC")
        (field (name "AUTHOR") "CERN DEM JLC")
      )
      (libsource (lib "Resistors") (part "Resistor"))
    )
    (comp (ref "R327")
      (value "4k7")
      (footprint "RESC1005X40N")
      (description "Resistor - 1%")
      (fields
        (field (name "MANUFACTURER PART NUMBER") "R0402_4K7_1%_0.0625W_100PPM")
        (field (name "MANUFACTURER") "GENERIC")
        (field (name "AUTHOR") "CERN DEM JLC")
      )
      (libsource (lib "Resistors") (part "Resistor - 1%"))
    )
    (comp (ref "R328")
      (value "4k7")
      (footprint "RESC1005X40N")
      (description "Resistor - 1%")
      (fields
        (field (name "MANUFACTURER PART NUMBER") "R0402_4K7_1%_0.0625W_100PPM")
        (field (name "MANUFACTURER") "GENERIC")
        (field (name "AUTHOR") "CERN DEM JLC")
      )
      (libsource (lib "Resistors") (part "Resistor - 1%"))
    )
    (comp (ref "R330")
      (value "0")
      (footprint "RESC1005X40N")
      (description "Resistor")
      (fields
        (field (name "MANUFACTURER PART NUMBER") "R0402_0R_JUMPER")
        (field (name "MANUFACTURER") "GENERIC")
        (field (name "AUTHOR") "CERN DEM JLC")
      )
      (libsource (lib "Resistors") (part "Resistor"))
    )
    (comp (ref "R331")
      (value "49R9")
      (footprint "RESC1005X40N")
      (description "Resistor - 1%")
      (fields
        (field (name "MANUFACTURER PART NUMBER") "R0402_49R9_1%_0.0625W_100PPM")
        (field (name "MANUFACTURER") "GENERIC")
        (field (name "AUTHOR") "CERN DEM JLC")
      )
      (libsource (lib "Resistors") (part "Resistor - 1%"))
    )
    (comp (ref "R332")
      (value "49R9")
      (footprint "RESC1005X40N")
      (description "Resistor - 1%")
      (fields
        (field (name "MANUFACTURER PART NUMBER") "R0402_49R9_1%_0.0625W_100PPM")
        (field (name "MANUFACTURER") "GENERIC")
        (field (name "AUTHOR") "CERN DEM JLC")
      )
      (libsource (lib "Resistors") (part "Resistor - 1%"))
    )
    (comp (ref "R333")
      (value "0")
      (footprint "RESC1005X40N")
      (description "Resistor")
      (fields
        (field (name "MANUFACTURER PART NUMBER") "R0402_0R_JUMPER")
        (field (name "MANUFACTURER") "GENERIC")
        (field (name "AUTHOR") "CERN DEM JLC")
      )
      (libsource (lib "Resistors") (part "Resistor"))
    )
    (comp (ref "R349")
      (value "150")
      (footprint "RESC1005X40N")
      (description "Resistor - 1%")
      (fields
        (field (name "MANUFACTURER PART NUMBER") "R0402_150R_1%_0.0625W_100PPM")
        (field (name "MANUFACTURER") "GENERIC")
        (field (name "AUTHOR") "CERN DEM JLC")
      )
      (libsource (lib "Resistors") (part "Resistor - 1%"))
    )
    (comp (ref "R350")
      (value "200")
      (footprint "RESC1005X40N")
      (description "Resistor - 1%")
      (fields
        (field (name "MANUFACTURER PART NUMBER") "R0402_200R_1%_0.0625W_100PPM")
        (field (name "MANUFACTURER") "GENERIC")
        (field (name "AUTHOR") "CERN DEM JLC")
      )
      (libsource (lib "Resistors") (part "Resistor - 1%"))
    )
    (comp (ref "R351")
      (value "200")
      (footprint "RESC1005X40N")
      (description "Resistor - 1%")
      (fields
        (field (name "MANUFACTURER PART NUMBER") "R0402_200R_1%_0.0625W_100PPM")
        (field (name "MANUFACTURER") "GENERIC")
        (field (name "AUTHOR") "CERN DEM JLC")
      )
      (libsource (lib "Resistors") (part "Resistor - 1%"))
    )
    (comp (ref "R352")
      (value "0")
      (footprint "RESC1005X40N")
      (description "Resistor")
      (fields
        (field (name "MANUFACTURER PART NUMBER") "R0402_0R_JUMPER")
        (field (name "MANUFACTURER") "GENERIC")
        (field (name "AUTHOR") "CERN DEM JLC")
      )
      (libsource (lib "Resistors") (part "Resistor"))
    )
    (comp (ref "R391")
      (value "0")
      (footprint "RESC1005X40N")
      (description "Resistor")
      (fields
        (field (name "MANUFACTURER PART NUMBER") "R0402_0R_JUMPER")
        (field (name "MANUFACTURER") "GENERIC")
        (field (name "AUTHOR") "CERN DEM JLC")
      )
      (libsource (lib "Resistors") (part "Resistor"))
    )
    (comp (ref "R419")
      (value "49R9")
      (footprint "RESC1005X40N")
      (description "Resistor - 1%")
      (fields
        (field (name "MANUFACTURER PART NUMBER") "R0402_49R9_1%_0.0625W_100PPM")
        (field (name "MANUFACTURER") "GENERIC")
        (field (name "AUTHOR") "CERN DEM JLC")
      )
      (libsource (lib "Resistors") (part "Resistor - 1%"))
    )
    (comp (ref "R454")
      (value "200")
      (footprint "RESC1005X40N")
      (description "Resistor - 1%")
      (fields
        (field (name "MANUFACTURER PART NUMBER") "R0402_200R_1%_0.0625W_100PPM")
        (field (name "MANUFACTURER") "GENERIC")
        (field (name "AUTHOR") "CERN DEM JLC")
      )
      (libsource (lib "Resistors") (part "Resistor - 1%"))
    )
    (comp (ref "R455")
      (value "49R9")
      (footprint "RESC1005X40N")
      (description "Resistor - 1%")
      (fields
        (field (name "MANUFACTURER PART NUMBER") "R0402_49R9_1%_0.0625W_100PPM")
        (field (name "MANUFACTURER") "GENERIC")
        (field (name "AUTHOR") "CERN DEM JLC")
      )
      (libsource (lib "Resistors") (part "Resistor - 1%"))
    )
    (comp (ref "TP8")
      (value "Test Point")
      (footprint "TPS127")
      (fields (field (name "PART NUMBER") "SMD_PAD_1.27X1.27MM") (field (name "AUTHOR") "CERN DEM JLC"))
      (libsource (lib "Eletro-mechanical") (part "Test Point"))
    )
    (comp (ref "TP9")
      (value "Test Point")
      (footprint "TPS127")
      (fields (field (name "PART NUMBER") "SMD_PAD_1.27X1.27MM") (field (name "AUTHOR") "CERN DEM JLC"))
      (libsource (lib "Eletro-mechanical") (part "Test Point"))
    )
    (comp (ref "TP10")
      (value "Test Point")
      (footprint "TPS127")
      (fields (field (name "PART NUMBER") "SMD_PAD_1.27X1.27MM") (field (name "AUTHOR") "CERN DEM JLC"))
      (libsource (lib "Eletro-mechanical") (part "Test Point"))
    )
    (comp (ref "TP11")
      (value "Test Point")
      (footprint "TPS127")
      (fields (field (name "PART NUMBER") "SMD_PAD_1.27X1.27MM") (field (name "AUTHOR") "CERN DEM JLC"))
      (libsource (lib "Eletro-mechanical") (part "Test Point"))
    )
    (comp (ref "TP12")
      (value "Test Point")
      (footprint "TPS127")
      (fields (field (name "PART NUMBER") "SMD_PAD_1.27X1.27MM") (field (name "AUTHOR") "CERN DEM JLC"))
      (libsource (lib "Eletro-mechanical") (part "Test Point"))
    )
    (comp (ref "TP13")
      (value "Test Point")
      (footprint "TPS127")
      (fields (field (name "PART NUMBER") "SMD_PAD_1.27X1.27MM") (field (name "AUTHOR") "CERN DEM JLC"))
      (libsource (lib "Eletro-mechanical") (part "Test Point"))
    )
    (comp (ref "TP14")
      (value "Test Point")
      (footprint "TPS127")
      (fields (field (name "PART NUMBER") "SMD_PAD_1.27X1.27MM") (field (name "AUTHOR") "CERN DEM JLC"))
      (libsource (lib "Eletro-mechanical") (part "Test Point"))
    )
    (comp (ref "TP15")
      (value "Test Point")
      (footprint "TPS127")
      (fields (field (name "PART NUMBER") "SMD_PAD_1.27X1.27MM") (field (name "AUTHOR") "CERN DEM JLC"))
      (libsource (lib "Eletro-mechanical") (part "Test Point"))
    )
    (comp (ref "TR2")
      (value "1:2")
      (footprint "XFMR_MINI-CIRCUITS_DB1627")
      (description "50 OHMS 10 to 4000 MHz RF Transformer")
      (fields
        (field (name "PART NUMBER") "XFMR_MINI-CIRCUITS_TCM2-43X+")
        (field (name "POWER") "0.4W")
        (field (name "MANUFACTURER PART NUMBER") "TCM2-43X+")
        (field (name "AUTHOR") "CERN DEM BC")
      )
      (libsource (lib "Inductors & Transformers") (part "XFMR_MINI-CIRCUITS_TCM2-43X"))
    )
  )
  (nets
    (net (code "7") (name "/AUX_CLOCK_C2_N") (class "Default")
      (node (ref "C108") (pin "2") (pinfunction "2_2") (pintype "passive"))
      (node (ref "R93") (pin "1") (pinfunction "1_1") (pintype "passive"))
    )
    (net (code "8") (name "/AUX_CLOCK_C2_P") (class "Default")
      (node (ref "C107") (pin "2") (pinfunction "2_2") (pintype "passive"))
      (node (ref "R93") (pin "2") (pinfunction "2_2") (pintype "passive"))
    )
    (net (code "9") (name "/CDR_CLK_CLEAN4_N") (class "Default")
      (node (ref "C575") (pin "1") (pinfunction "1_1") (pintype "passive"))
      (node (ref "IC16") (pin "12") (pinfunction "Q7_12") (pintype "output"))
      (node (ref "R319") (pin "1") (pinfunction "1_1") (pintype "passive"))
    )
    (net (code "10") (name "/CDR_CLK_CLEAN4_P") (class "Default")
      (node (ref "C572") (pin "2") (pinfunction "2_2") (pintype "passive"))
      (node (ref "IC16") (pin "11") (pinfunction "~{Q7}_11") (pintype "output"))
      (node (ref "R320") (pin "1") (pinfunction "1_1") (pintype "passive"))
    )
    (net (code "11") (name "/CLK_SEL") (class "Default")
      (node (ref "IC16") (pin "32") (pinfunction "IN_SEL_32") (pintype "input"))
    )
    (net (code "14") (name "/EN_P3V3_CLK") (class "Default")
      (node (ref "IC17") (pin "1") (pinfunction "EN_1") (pintype "power_in"))
    )
    (net (code "15") (name "/Helper_CLK_N") (class "Default")
      (node (ref "R332") (pin "2") (pinfunction "2_2") (pintype "passive"))
    )
    (net (code "16") (name "/Helper_CLK_P") (class "Default")
      (node (ref "R331") (pin "2") (pinfunction "2_2") (pintype "passive"))
    )
    (net (code "17") (name "/Helper_DCXO_OE") (class "Default")
      (node (ref "R333") (pin "2") (pinfunction "2_2") (pintype "passive"))
      (node (ref "R391") (pin "2") (pinfunction "2_2") (pintype "passive"))
    )
    (net (code "18") (name "/Helper_DCXO_SCL") (class "Default")
      (node (ref "OSC4") (pin "8") (pinfunction "SCL_8") (pintype "passive"))
      (node (ref "R328") (pin "1") (pinfunction "1_1") (pintype "passive"))
      (node (ref "TP13") (pin "1") (pinfunction "1_1") (pintype "bidirectional"))
    )
    (net (code "19") (name "/Helper_DCXO_SDA") (class "Default")
      (node (ref "OSC4") (pin "7") (pinfunction "SDA_7") (pintype "passive"))
      (node (ref "R327") (pin "1") (pinfunction "1_1") (pintype "passive"))
      (node (ref "TP12") (pin "1") (pinfunction "1_1") (pintype "bidirectional"))
    )
    (net (code "21") (name "/Main_DCXO_N") (class "Default")
      (node (ref "C557") (pin "2") (pinfunction "2_2") (pintype "passive"))
      (node (ref "C561") (pin "2") (pinfunction "2_2") (pintype "passive"))
      (node (ref "IC16") (pin "2") (pinfunction "~{CLK0}_2") (pintype "input"))
    )
    (net (code "22") (name "/Main_DCXO_OE") (class "Default")
      (node (ref "R277") (pin "2") (pinfunction "2_2") (pintype "passive"))
      (node (ref "R315") (pin "2") (pinfunction "2_2") (pintype "passive"))
    )
    (net (code "23") (name "/Main_DCXO_P") (class "Default")
      (node (ref "C556") (pin "2") (pinfunction "2_2") (pintype "passive"))
      (node (ref "IC16") (pin "1") (pinfunction "CLK0_1") (pintype "input"))
    )
    (net (code "24") (name "/Main_DCXO_SCL") (class "Default")
      (node (ref "OSC3") (pin "8") (pinfunction "SCL_8") (pintype "passive"))
      (node (ref "R271") (pin "1") (pinfunction "1_1") (pintype "passive"))
      (node (ref "TP11") (pin "1") (pinfunction "1_1") (pintype "bidirectional"))
    )
    (net (code "25") (name "/Main_DCXO_SDA") (class "Default")
      (node (ref "OSC3") (pin "7") (pinfunction "SDA_7") (pintype "passive"))
      (node (ref "R270") (pin "1") (pinfunction "1_1") (pintype "passive"))
      (node (ref "TP10") (pin "1") (pinfunction "1_1") (pintype "bidirectional"))
    )
    (net (code "26") (name "/P3V3_CLKDIS4F") (class "Default")
      (node (ref "C565") (pin "1") (pinfunction "1_1") (pintype "passive"))
      (node (ref "C566") (pin "2") (pinfunction "2_2") (pintype "passive"))
      (node (ref "C567") (pin "2") (pinfunction "2_2") (pintype "passive"))
      (node (ref "C568") (pin "2") (pinfunction "2_2") (pintype "passive"))
      (node (ref "C569") (pin "2") (pinfunction "2_2") (pintype "passive"))
      (node (ref "C570") (pin "2") (pinfunction "2_2") (pintype "passive"))
      (node (ref "C571") (pin "2") (pinfunction "2_2") (pintype "passive"))
      (node (ref "IC16") (pin "10") (pinfunction "VCC_10") (pintype "power_in"))
      (node (ref "IC16") (pin "15") (pinfunction "VCC_15") (pintype "power_in"))
      (node (ref "IC16") (pin "16") (pinfunction "VCC_16") (pintype "power_in"))
      (node (ref "IC16") (pin "25") (pinfunction "VCC_25") (pintype "power_in"))
      (node (ref "IC16") (pin "26") (pinfunction "VCC_26") (pintype "power_in"))
      (node (ref "IC16") (pin "31") (pinfunction "VCC_31") (pintype "power_in"))
      (node (ref "L32") (pin "2") (pinfunction "2_2") (pintype "passive"))
    )
    (net (code "27") (name "/P5V0_LDO_IN") (class "Default")
      (node (ref "C515") (pin "2") (pinfunction "2_2") (pintype "passive"))
      (node (ref "IC17") (pin "2") (pinfunction "IN_2") (pintype "input"))
      (node (ref "L4") (pin "2") (pinfunction "2_2") (pintype "passive"))
    )
    (net (code "28") (name "/REC_CLOCK_C_N") (class "Default")
      (node (ref "C99") (pin "2") (pinfunction "2_2") (pintype "passive"))
      (node (ref "R84") (pin "1") (pinfunction "1_1") (pintype "passive"))
    )
    (net (code "29") (name "/REC_CLOCK_C_P") (class "Default")
      (node (ref "C98") (pin "2") (pinfunction "2_2") (pintype "passive"))
      (node (ref "R84") (pin "2") (pinfunction "2_2") (pintype "passive"))
    )
    (net (code "30") (name "/REC_CLOCK_N") (class "Default")
      (node (ref "C99") (pin "1") (pinfunction "1_1") (pintype "passive"))
      (node (ref "IC18") (pin "17") (pinfunction "CKIN1-_17") (pintype "input"))
    )
    (net (code "31") (name "/REC_CLOCK_P") (class "Default")
      (node (ref "C98") (pin "1") (pinfunction "1_1") (pintype "passive"))
      (node (ref "IC18") (pin "16") (pinfunction "CKIN1+_16") (pintype "input"))
    )
    (net (code "32") (name "/REF_LOC_N") (class "Default")
      (node (ref "C110") (pin "2") (pinfunction "2_2") (pintype "passive"))
      (node (ref "IC16") (pin "6") (pinfunction "~{CLK1}_6") (pintype "input"))
    )
    (net (code "33") (name "/REF_LOC_P") (class "Default")
      (node (ref "C109") (pin "2") (pinfunction "2_2") (pintype "passive"))
      (node (ref "IC16") (pin "5") (pinfunction "CLK1_5") (pintype "input"))
    )
    (net (code "34") (name "/SI5324_INT_ALM") (class "Default")
      (node (ref "IC18") (pin "3") (pinfunction "INT_C1B_3") (pintype "output"))
    )
    (net (code "35") (name "/SI5324_RST") (class "Default")
      (node (ref "IC18") (pin "1") (pinfunction "~{RST}_1") (pintype "input"))
    )
    (net (code "36") (name "/SI5324_SCL") (class "Default")
      (node (ref "IC18") (pin "22") (pinfunction "SCL_22") (pintype "input"))
      (node (ref "TP9") (pin "1") (pinfunction "1_1") (pintype "bidirectional"))
    )
    (net (code "37") (name "/SI5324_SDA") (class "Default")
      (node (ref "IC18") (pin "23") (pinfunction "SDA_SDO_23") (pintype "bidirectional"))
      (node (ref "TP8") (pin "1") (pinfunction "1_1") (pintype "bidirectional"))
    )
    (net (code "38") (name "/SI5324_VDD") (class "Default")
      (node (ref "C111") (pin "2") (pinfunction "2_2") (pintype "passive"))
      (node (ref "C355") (pin "1") (pinfunction "1_1") (pintype "passive"))
      (node (ref "C96") (pin "2") (pinfunction "2_2") (pintype "passive"))
      (node (ref "C97") (pin "2") (pinfunction "2_2") (pintype "passive"))
      (node (ref "IC18") (pin "10") (pinfunction "VDD_10") (pintype "power_in"))
      (node (ref "IC18") (pin "32") (pinfunction "VDD_32") (pintype "power_in"))
      (node (ref "IC18") (pin "5") (pinfunction "VDD_5") (pintype "power_in"))
      (node (ref "L2") (pin "2") (pinfunction "2_2") (pintype "passive"))
    )
    (net (code "39") (name "/SI5324_XTAL_XA") (class "Default")
      (node (ref "IC18") (pin "6") (pinfunction "XA_6") (pintype "input"))
      (node (ref "Q1") (pin "3") (pinfunction "X_3") (pintype "passive"))
    )
    (net (code "40") (name "/SI5324_XTAL_XB") (class "Default")
      (node (ref "IC18") (pin "7") (pinfunction "XB_7") (pintype "input"))
      (node (ref "Q1") (pin "1") (pinfunction "X_1") (pintype "passive"))
    )
    (net (code "44") (name "GND") (class "Default")
      (node (ref "C111") (pin "1") (pinfunction "1_1") (pintype "passive"))
      (node (ref "C324") (pin "1") (pinfunction "1_1") (pintype "passive"))
      (node (ref "C355") (pin "2") (pinfunction "2_2") (pintype "passive"))
      (node (ref "C513") (pin "1") (pinfunction "1_1") (pintype "passive"))
      (node (ref "C514") (pin "1") (pinfunction "1_1") (pintype "passive"))
      (node (ref "C515") (pin "1") (pinfunction "1_1") (pintype "passive"))
      (node (ref "C548") (pin "1") (pinfunction "1_1") (pintype "passive"))
      (node (ref "C551") (pin "1") (pinfunction "1_1") (pintype "passive"))
      (node (ref "C552") (pin "1") (pinfunction "1_1") (pintype "passive"))
      (node (ref "C555") (pin "1") (pinfunction "1_1") (pintype "passive"))
      (node (ref "C560") (pin "1") (pinfunction "1_1") (pintype "passive"))
      (node (ref "C561") (pin "1") (pinfunction "1_1") (pintype "passive"))
      (node (ref "C562") (pin "1") (pinfunction "1_1") (pintype "passive"))
      (node (ref "C565") (pin "2") (pinfunction "2_2") (pintype "passive"))
      (node (ref "C566") (pin "1") (pinfunction "1_1") (pintype "passive"))
      (node (ref "C567") (pin "1") (pinfunction "1_1") (pintype "passive"))
      (node (ref "C568") (pin "1") (pinfunction "1_1") (pintype "passive"))
      (node (ref "C569") (pin "1") (pinfunction "1_1") (pintype "passive"))
      (node (ref "C570") (pin "1") (pinfunction "1_1") (pintype "passive"))
      (node (ref "C571") (pin "1") (pinfunction "1_1") (pintype "passive"))
      (node (ref "C573") (pin "1") (pinfunction "1_1") (pintype "passive"))
      (node (ref "C574") (pin "1") (pinfunction "1_1") (pintype "passive"))
      (node (ref "C578") (pin "1") (pinfunction "1_1") (pintype "passive"))
      (node (ref "C96") (pin "1") (pinfunction "1_1") (pintype "passive"))
      (node (ref "C97") (pin "1") (pinfunction "1_1") (pintype "passive"))
      (node (ref "IC16") (pin "33") (pinfunction "VEE_33") (pintype "power_in"))
      (node (ref "IC17") (pin "3") (pinfunction "GND_3") (pintype "power_in"))
      (node (ref "IC17") (pin "6") (pinfunction "GND_6") (pintype "power_in"))
      (node (ref "IC18") (pin "19") (pinfunction "GND_19") (pintype "power_in"))
      (node (ref "IC18") (pin "20") (pinfunction "GND_20") (pintype "power_in"))
      (node (ref "IC18") (pin "24") (pinfunction "A0_24") (pintype "input"))
      (node (ref "IC18") (pin "25") (pinfunction "A1_25") (pintype "input"))
      (node (ref "IC18") (pin "26") (pinfunction "A2_~{SS}_26") (pintype "input"))
      (node (ref "IC18") (pin "31") (pinfunction "GND_31") (pintype "power_in"))
      (node (ref "IC18") (pin "36") (pinfunction "CMODE_36") (pintype "input"))
      (node (ref "IC18") (pin "37") (pinfunction "GND_37") (pintype "power_in"))
      (node (ref "IC18") (pin "8") (pinfunction "GND_8") (pintype "power_in"))
      (node (ref "J10") (pin "2") (pinfunction "2_2") (pintype "bidirectional"))
      (node (ref "J16") (pin "2") (pinfunction "2_2") (pintype "bidirectional"))
      (node (ref "J17") (pin "2") (pinfunction "2_2") (pintype "bidirectional"))
      (node (ref "J24") (pin "2") (pinfunction "2_2") (pintype "bidirectional"))
      (node (ref "OSC3") (pin "3") (pinfunction "GND_3") (pintype "passive"))
      (node (ref "OSC4") (pin "3") (pinfunction "GND_3") (pintype "passive"))
      (node (ref "Q1") (pin "2") (pinfunction "GND_2") (pintype "power_in"))
      (node (ref "Q1") (pin "4") (pinfunction "GND_4") (pintype "power_in"))
      (node (ref "R259") (pin "1") (pinfunction "1_1") (pintype "passive"))
      (node (ref "R261") (pin "2") (pinfunction "2_2") (pintype "passive"))
      (node (ref "R263") (pin "2") (pinfunction "2_2") (pintype "passive"))
      (node (ref "R265") (pin "2") (pinfunction "2_2") (pintype "passive"))
      (node (ref "R267") (pin "2") (pinfunction "2_2") (pintype "passive"))
      (node (ref "R272") (pin "2") (pinfunction "2_2") (pintype "passive"))
      (node (ref "R279") (pin "2") (pinfunction "2_2") (pintype "passive"))
      (node (ref "R282") (pin "1") (pinfunction "1_1") (pintype "passive"))
      (node (ref "R293") (pin "1") (pinfunction "1_1") (pintype "passive"))
      (node (ref "R310") (pin "2") (pinfunction "2_2") (pintype "passive"))
      (node (ref "R316") (pin "2") (pinfunction "2_2") (pintype "passive"))
      (node (ref "R319") (pin "2") (pinfunction "2_2") (pintype "passive"))
      (node (ref "R320") (pin "2") (pinfunction "2_2") (pintype "passive"))
      (node (ref "R350") (pin "1") (pinfunction "1_1") (pintype "passive"))
      (node (ref "R351") (pin "1") (pinfunction "1_1") (pintype "passive"))
      (node (ref "R352") (pin "1") (pinfunction "1_1") (pintype "passive"))
      (node (ref "R39") (pin "2") (pinfunction "2_2") (pintype "passive"))
      (node (ref "R454") (pin "2") (pinfunction "2_2") (pintype "passive"))
      (node (ref "R85") (pin "1") (pinfunction "1_1") (pintype "passive"))
      (node (ref "TR2") (pin "1") (pinfunction "P1_1") (pintype "passive"))
      (node (ref "TR2") (pin "2") (pinfunction "P1_2") (pintype "passive"))
      (node (ref "TR2") (pin "5") (pinfunction "NC_5") (pintype "passive"))
    )
    (net (code "45") (name "Net-(C543-Pad1)") (class "Default")
      (node (ref "C543") (pin "1") (pinfunction "1_1") (pintype "passive"))
      (node (ref "R419") (pin "2") (pinfunction "2_2") (pintype "passive"))
    )
    (net (code "46") (name "Net-(C544-Pad1)") (class "Default")
      (node (ref "C544") (pin "1") (pinfunction "1_1") (pintype "passive"))
      (node (ref "R455") (pin "2") (pinfunction "2_2") (pintype "passive"))
    )
    (net (code "47") (name "Net-(C545-Pad1)") (class "Default")
      (node (ref "C545") (pin "1") (pinfunction "1_1") (pintype "passive"))
      (node (ref "J10") (pin "1") (pinfunction "1_1") (pintype "bidirectional"))
    )
    (net (code "48") (name "Net-(C545-Pad2)") (class "Default")
      (node (ref "C545") (pin "2") (pinfunction "2_2") (pintype "passive"))
      (node (ref "R258") (pin "2") (pinfunction "2_2") (pintype "passive"))
      (node (ref "TR2") (pin "3") (pinfunction "P1_3") (pintype "passive"))
    )
    (net (code "49") (name "Net-(C546-Pad1)") (class "Default")
      (node (ref "C546") (pin "1") (pinfunction "1_1") (pintype "passive"))
      (node (ref "R258") (pin "1") (pinfunction "1_1") (pintype "passive"))
      (node (ref "TR2") (pin "6") (pinfunction "S1_6") (pintype "passive"))
    )
    (net (code "50") (name "Net-(C547-Pad1)") (class "Default")
      (node (ref "C547") (pin "1") (pinfunction "1_1") (pintype "passive"))
      (node (ref "R259") (pin "2") (pinfunction "2_2") (pintype "passive"))
      (node (ref "TR2") (pin "4") (pinfunction "S1_4") (pintype "passive"))
    )
    (net (code "51") (name "Net-(C548-Pad2)") (class "Default")
      (node (ref "C548") (pin "2") (pinfunction "2_2") (pintype "passive"))
      (node (ref "R260") (pin "2") (pinfunction "2_2") (pintype "passive"))
      (node (ref "R270") (pin "2") (pinfunction "2_2") (pintype "passive"))
      (node (ref "R271") (pin "2") (pinfunction "2_2") (pintype "passive"))
      (node (ref "R327") (pin "2") (pinfunction "2_2") (pintype "passive"))
      (node (ref "R328") (pin "2") (pinfunction "2_2") (pintype "passive"))
    )
    (net (code "52") (name "Net-(C549-Pad1)") (class "Default")
      (node (ref "C549") (pin "1") (pinfunction "1_1") (pintype "passive"))
      (node (ref "R262") (pin "2") (pinfunction "2_2") (pintype "passive"))
    )
    (net (code "53") (name "Net-(C550-Pad1)") (class "Default")
      (node (ref "C550") (pin "1") (pinfunction "1_1") (pintype "passive"))
      (node (ref "R264") (pin "2") (pinfunction "2_2") (pintype "passive"))
    )
    (net (code "54") (name "Net-(C553-Pad1)") (class "Default")
      (node (ref "C553") (pin "1") (pinfunction "1_1") (pintype "passive"))
      (node (ref "R266") (pin "2") (pinfunction "2_2") (pintype "passive"))
    )
    (net (code "55") (name "Net-(C554-Pad1)") (class "Default")
      (node (ref "C554") (pin "1") (pinfunction "1_1") (pintype "passive"))
      (node (ref "R268") (pin "2") (pinfunction "2_2") (pintype "passive"))
    )
    (net (code "56") (name "Net-(C556-Pad1)") (class "Default")
      (node (ref "C556") (pin "1") (pinfunction "1_1") (pintype "passive"))
      (node (ref "R278") (pin "1") (pinfunction "1_1") (pintype "passive"))
      (node (ref "R282") (pin "2") (pinfunction "2_2") (pintype "passive"))
    )
    (net (code "57") (name "Net-(C558-Pad1)") (class "Default")
      (node (ref "C558") (pin "1") (pinfunction "1_1") (pintype "passive"))
      (node (ref "R276") (pin "2") (pinfunction "2_2") (pintype "passive"))
    )
    (net (code "58") (name "Net-(C559-Pad1)") (class "Default")
      (node (ref "C559") (pin "1") (pinfunction "1_1") (pintype "passive"))
      (node (ref "R280") (pin "2") (pinfunction "2_2") (pintype "passive"))
    )
    (net (code "59") (name "Net-(C563-Pad1)") (class "Default")
      (node (ref "C563") (pin "1") (pinfunction "1_1") (pintype "passive"))
      (node (ref "R311") (pin "2") (pinfunction "2_2") (pintype "passive"))
    )
    (net (code "60") (name "Net-(C564-Pad1)") (class "Default")
      (node (ref "C564") (pin "1") (pinfunction "1_1") (pintype "passive"))
      (node (ref "R317") (pin "2") (pinfunction "2_2") (pintype "passive"))
    )
    (net (code "61") (name "Net-(C572-Pad1)") (class "Default")
      (node (ref "C572") (pin "1") (pinfunction "1_1") (pintype "passive"))
      (node (ref "J17") (pin "1") (pinfunction "1_1") (pintype "bidirectional"))
    )
    (net (code "62") (name "Net-(C575-Pad2)") (class "Default")
      (node (ref "C575") (pin "2") (pinfunction "2_2") (pintype "passive"))
      (node (ref "J24") (pin "1") (pinfunction "1_1") (pintype "bidirectional"))
    )
    (net (code "63") (name "Net-(C576-Pad1)") (class "Default")
      (node (ref "C576") (pin "1") (pinfunction "1_1") (pintype "passive"))
      (node (ref "R330") (pin "2") (pinfunction "2_2") (pintype "passive"))
      (node (ref "R349") (pin "1") (pinfunction "1_1") (pintype "passive"))
      (node (ref "R350") (pin "2") (pinfunction "2_2") (pintype "passive"))
    )
    (net (code "64") (name "Net-(C576-Pad2)") (class "Default")
      (node (ref "C576") (pin "2") (pinfunction "2_2") (pintype "passive"))
      (node (ref "R324") (pin "2") (pinfunction "2_2") (pintype "passive"))
      (node (ref "R330") (pin "1") (pinfunction "1_1") (pintype "passive"))
      (node (ref "R331") (pin "1") (pinfunction "1_1") (pintype "passive"))
    )
    (net (code "65") (name "Net-(C577-Pad2)") (class "Default")
      (node (ref "C577") (pin "2") (pinfunction "2_2") (pintype "passive"))
      (node (ref "R332") (pin "1") (pinfunction "1_1") (pintype "passive"))
      (node (ref "R352") (pin "2") (pinfunction "2_2") (pintype "passive"))
    )
    (net (code "66") (name "Net-(IC16-Q0)") (class "Default")
      (node (ref "IC16") (pin "30") (pinfunction "Q0_30") (pintype "output"))
      (node (ref "R261") (pin "1") (pinfunction "1_1") (pintype "passive"))
      (node (ref "R262") (pin "1") (pinfunction "1_1") (pintype "passive"))
    )
    (net (code "67") (name "Net-(IC16-Q1)") (class "Default")
      (node (ref "IC16") (pin "28") (pinfunction "Q1_28") (pintype "output"))
      (node (ref "R265") (pin "1") (pinfunction "1_1") (pintype "passive"))
      (node (ref "R266") (pin "1") (pinfunction "1_1") (pintype "passive"))
    )
    (net (code "68") (name "Net-(IC16-Q3)") (class "Default")
      (node (ref "IC16") (pin "22") (pinfunction "Q3_22") (pintype "output"))
      (node (ref "R272") (pin "1") (pinfunction "1_1") (pintype "passive"))
      (node (ref "R276") (pin "1") (pinfunction "1_1") (pintype "passive"))
    )
    (net (code "69") (name "Net-(IC16-Q4)") (class "Default")
      (node (ref "IC16") (pin "20") (pinfunction "Q4_20") (pintype "output"))
      (node (ref "R39") (pin "1") (pinfunction "1_1") (pintype "passive"))
      (node (ref "R419") (pin "1") (pinfunction "1_1") (pintype "passive"))
    )
    (net (code "70") (name "Net-(IC16-Q5)") (class "Default")
      (node (ref "IC16") (pin "18") (pinfunction "Q5_18") (pintype "output"))
      (node (ref "R310") (pin "1") (pinfunction "1_1") (pintype "passive"))
      (node (ref "R311") (pin "1") (pinfunction "1_1") (pintype "passive"))
    )
    (net (code "71") (name "Net-(IC16-VREF0)") (class "Default")
      (node (ref "IC16") (pin "3") (pinfunction "VREF0_3") (pintype "input"))
      (node (ref "R269") (pin "2") (pinfunction "2_2") (pintype "passive"))
    )
    (net (code "72") (name "Net-(IC16-VREF1)") (class "Default")
      (node (ref "IC16") (pin "8") (pinfunction "VREF1_8") (pintype "input"))
      (node (ref "R281") (pin "2") (pinfunction "2_2") (pintype "passive"))
    )
    (net (code "73") (name "Net-(IC16-VT0)") (class "Default")
      (node (ref "C555") (pin "2") (pinfunction "2_2") (pintype "passive"))
      (node (ref "IC16") (pin "4") (pinfunction "VT0_4") (pintype "passive"))
      (node (ref "R269") (pin "1") (pinfunction "1_1") (pintype "passive"))
    )
    (net (code "74") (name "Net-(IC16-VT1)") (class "Default")
      (node (ref "C560") (pin "2") (pinfunction "2_2") (pintype "passive"))
      (node (ref "IC16") (pin "7") (pinfunction "VT1_7") (pintype "passive"))
      (node (ref "R281") (pin "1") (pinfunction "1_1") (pintype "passive"))
    )
    (net (code "75") (name "Net-(IC16-~{Q0})") (class "Default")
      (node (ref "IC16") (pin "29") (pinfunction "~{Q0}_29") (pintype "output"))
      (node (ref "R263") (pin "1") (pinfunction "1_1") (pintype "passive"))
      (node (ref "R264") (pin "1") (pinfunction "1_1") (pintype "passive"))
    )
    (net (code "76") (name "Net-(IC16-~{Q1})") (class "Default")
      (node (ref "IC16") (pin "27") (pinfunction "~{Q1}_27") (pintype "output"))
      (node (ref "R267") (pin "1") (pinfunction "1_1") (pintype "passive"))
      (node (ref "R268") (pin "1") (pinfunction "1_1") (pintype "passive"))
    )
    (net (code "77") (name "Net-(IC16-~{Q3})") (class "Default")
      (node (ref "IC16") (pin "21") (pinfunction "~{Q3}_21") (pintype "output"))
      (node (ref "R279") (pin "1") (pinfunction "1_1") (pintype "passive"))
      (node (ref "R280") (pin "1") (pinfunction "1_1") (pintype "passive"))
    )
    (net (code "78") (name "Net-(IC16-~{Q4})") (class "Default")
      (node (ref "IC16") (pin "19") (pinfunction "~{Q4}_19") (pintype "output"))
      (node (ref "R454") (pin "1") (pinfunction "1_1") (pintype "passive"))
      (node (ref "R455") (pin "1") (pinfunction "1_1") (pintype "passive"))
    )
    (net (code "79") (name "Net-(IC16-~{Q5})") (class "Default")
      (node (ref "IC16") (pin "17") (pinfunction "~{Q5}_17") (pintype "output"))
      (node (ref "R316") (pin "1") (pinfunction "1_1") (pintype "passive"))
      (node (ref "R317") (pin "1") (pinfunction "1_1") (pintype "passive"))
    )
    (net (code "80") (name "Net-(IC17-NR)") (class "Default")
      (node (ref "C324") (pin "2") (pinfunction "2_2") (pintype "passive"))
      (node (ref "IC17") (pin "5") (pinfunction "NR_5") (pintype "passive"))
    )
    (net (code "81") (name "Net-(IC18-CKIN2+)") (class "Default")
      (node (ref "C107") (pin "1") (pinfunction "1_1") (pintype "passive"))
      (node (ref "IC18") (pin "12") (pinfunction "CKIN2+_12") (pintype "input"))
    )
    (net (code "82") (name "Net-(IC18-CKIN2-)") (class "Default")
      (node (ref "C108") (pin "1") (pinfunction "1_1") (pintype "passive"))
      (node (ref "IC18") (pin "13") (pinfunction "CKIN2-_13") (pintype "input"))
    )
    (net (code "83") (name "Net-(IC18-CKOUT2+)") (class "Default")
      (node (ref "C109") (pin "1") (pinfunction "1_1") (pintype "passive"))
      (node (ref "IC18") (pin "35") (pinfunction "CKOUT2+_35") (pintype "output"))
      (node (ref "TP14") (pin "1") (pinfunction "1_1") (pintype "bidirectional"))
    )
    (net (code "84") (name "Net-(IC18-CKOUT2-)") (class "Default")
      (node (ref "C110") (pin "1") (pinfunction "1_1") (pintype "passive"))
      (node (ref "IC18") (pin "34") (pinfunction "CKOUT2-_34") (pintype "output"))
      (node (ref "TP15") (pin "1") (pinfunction "1_1") (pintype "bidirectional"))
    )
    (net (code "85") (name "Net-(IC18-CS_CA)") (class "Default")
      (node (ref "IC18") (pin "21") (pinfunction "CS_CA_21") (pintype "bidirectional"))
      (node (ref "R85") (pin "2") (pinfunction "2_2") (pintype "passive"))
    )
    (net (code "86") (name "Net-(J16-Pad1)") (class "Default")
      (node (ref "J16") (pin "1") (pinfunction "1_1") (pintype "bidirectional"))
      (node (ref "R324") (pin "1") (pinfunction "1_1") (pintype "passive"))
    )
    (net (code "87") (name "Net-(OSC3-CLK+)") (class "Default")
      (node (ref "OSC3") (pin "4") (pinfunction "CLK+_4") (pintype "passive"))
      (node (ref "R278") (pin "2") (pinfunction "2_2") (pintype "passive"))
    )
    (net (code "88") (name "Net-(OSC3-CLK-)") (class "Default")
      (node (ref "C557") (pin "1") (pinfunction "1_1") (pintype "passive"))
      (node (ref "OSC3") (pin "5") (pinfunction "CLK-_5") (pintype "passive"))
      (node (ref "R293") (pin "2") (pinfunction "2_2") (pintype "passive"))
    )
    (net (code "89") (name "Net-(OSC3-NC)") (class "Default")
      (node (ref "OSC3") (pin "2") (pinfunction "NC_2") (pintype "passive"))
      (node (ref "R315") (pin "1") (pinfunction "1_1") (pintype "passive"))
    )
    (net (code "90") (name "Net-(OSC3-OE)") (class "Default")
      (node (ref "OSC3") (pin "1") (pinfunction "OE_1") (pintype "passive"))
      (node (ref "R277") (pin "1") (pinfunction "1_1") (pintype "passive"))
    )
    (net (code "91") (name "Net-(OSC3-VDD)") (class "Default")
      (node (ref "C551") (pin "2") (pinfunction "2_2") (pintype "passive"))
      (node (ref "C552") (pin "2") (pinfunction "2_2") (pintype "passive"))
      (node (ref "C562") (pin "2") (pinfunction "2_2") (pintype "passive"))
      (node (ref "L31") (pin "2") (pinfunction "2_2") (pintype "passive"))
      (node (ref "OSC3") (pin "6") (pinfunction "VDD_6") (pintype "passive"))
    )
    (net (code "92") (name "Net-(OSC4-CLK+)") (class "Default")
      (node (ref "OSC4") (pin "4") (pinfunction "CLK+_4") (pintype "passive"))
      (node (ref "R349") (pin "2") (pinfunction "2_2") (pintype "passive"))
    )
    (net (code "93") (name "Net-(OSC4-CLK-)") (class "Default")
      (node (ref "C577") (pin "1") (pinfunction "1_1") (pintype "passive"))
      (node (ref "OSC4") (pin "5") (pinfunction "CLK-_5") (pintype "passive"))
      (node (ref "R351") (pin "2") (pinfunction "2_2") (pintype "passive"))
    )
    (net (code "94") (name "Net-(OSC4-NC)") (class "Default")
      (node (ref "OSC4") (pin "2") (pinfunction "NC_2") (pintype "passive"))
      (node (ref "R391") (pin "1") (pinfunction "1_1") (pintype "passive"))
    )
    (net (code "95") (name "Net-(OSC4-OE)") (class "Default")
      (node (ref "OSC4") (pin "1") (pinfunction "OE_1") (pintype "passive"))
      (node (ref "R333") (pin "1") (pinfunction "1_1") (pintype "passive"))
    )
    (net (code "96") (name "Net-(OSC4-VDD)") (class "Default")
      (node (ref "C573") (pin "2") (pinfunction "2_2") (pintype "passive"))
      (node (ref "C574") (pin "2") (pinfunction "2_2") (pintype "passive"))
      (node (ref "C578") (pin "2") (pinfunction "2_2") (pintype "passive"))
      (node (ref "L33") (pin "2") (pinfunction "2_2") (pintype "passive"))
      (node (ref "OSC4") (pin "6") (pinfunction "VDD_6") (pintype "passive"))
    )
    (net (code "97") (name "P3V3") (class "Default")
      (node (ref "R260") (pin "1") (pinfunction "1_1") (pintype "passive"))
    )
    (net (code "98") (name "P3V3_CLK") (class "Default")
      (node (ref "C513") (pin "2") (pinfunction "2_2") (pintype "passive"))
      (node (ref "C514") (pin "2") (pinfunction "2_2") (pintype "passive"))
      (node (ref "IC17") (pin "4") (pinfunction "OUT_4") (pintype "power_in"))
      (node (ref "L2") (pin "1") (pinfunction "1_1") (pintype "passive"))
      (node (ref "L31") (pin "1") (pinfunction "1_1") (pintype "passive"))
      (node (ref "L32") (pin "1") (pinfunction "1_1") (pintype "passive"))
      (node (ref "L33") (pin "1") (pinfunction "1_1") (pintype "passive"))
    )
    (net (code "99") (name "P5V0") (class "Default")
      (node (ref "L4") (pin "1") (pinfunction "1_1") (pintype "passive"))
    )
    (net (code "100") (name "unconnected-(C543-Pad2)") (class "Default")
      (node (ref "C543") (pin "2") (pinfunction "2_2") (pintype "passive"))
    )
    (net (code "101") (name "unconnected-(C544-Pad2)") (class "Default")
      (node (ref "C544") (pin "2") (pinfunction "2_2") (pintype "passive"))
    )
    (net (code "102") (name "unconnected-(C546-Pad2)") (class "Default")
      (node (ref "C546") (pin "2") (pinfunction "2_2") (pintype "passive"))
    )
    (net (code "103") (name "unconnected-(C547-Pad2)") (class "Default")
      (node (ref "C547") (pin "2") (pinfunction "2_2") (pintype "passive"))
    )
    (net (code "104") (name "unconnected-(C549-Pad2)") (class "Default")
      (node (ref "C549") (pin "2") (pinfunction "2_2") (pintype "passive"))
    )
    (net (code "105") (name "unconnected-(C550-Pad2)") (class "Default")
      (node (ref "C550") (pin "2") (pinfunction "2_2") (pintype "passive"))
    )
    (net (code "106") (name "unconnected-(C553-Pad2)") (class "Default")
      (node (ref "C553") (pin "2") (pinfunction "2_2") (pintype "passive"))
    )
    (net (code "107") (name "unconnected-(C554-Pad2)") (class "Default")
      (node (ref "C554") (pin "2") (pinfunction "2_2") (pintype "passive"))
    )
    (net (code "108") (name "unconnected-(C558-Pad2)") (class "Default")
      (node (ref "C558") (pin "2") (pinfunction "2_2") (pintype "passive"))
    )
    (net (code "109") (name "unconnected-(C559-Pad2)") (class "Default")
      (node (ref "C559") (pin "2") (pinfunction "2_2") (pintype "passive"))
    )
    (net (code "110") (name "unconnected-(C563-Pad2)") (class "Default")
      (node (ref "C563") (pin "2") (pinfunction "2_2") (pintype "passive"))
    )
    (net (code "111") (name "unconnected-(C564-Pad2)") (class "Default")
      (node (ref "C564") (pin "2") (pinfunction "2_2") (pintype "passive"))
    )
    (net (code "112") (name "unconnected-(IC16-NC-Pad9)") (class "Default")
      (node (ref "IC16") (pin "9") (pinfunction "NC_9") (pintype "passive+no_connect"))
    )
    (net (code "113") (name "unconnected-(IC16-Q2-Pad24)") (class "Default")
      (node (ref "IC16") (pin "24") (pinfunction "Q2_24") (pintype "output"))
    )
    (net (code "114") (name "unconnected-(IC16-Q6-Pad14)") (class "Default")
      (node (ref "IC16") (pin "14") (pinfunction "Q6_14") (pintype "output+no_connect"))
    )
    (net (code "115") (name "unconnected-(IC16-~{Q2}-Pad23)") (class "Default")
      (node (ref "IC16") (pin "23") (pinfunction "~{Q2}_23") (pintype "output"))
    )
    (net (code "116") (name "unconnected-(IC16-~{Q6}-Pad13)") (class "Default")
      (node (ref "IC16") (pin "13") (pinfunction "~{Q6}_13") (pintype "output+no_connect"))
    )
    (net (code "117") (name "unconnected-(IC18-C2B-Pad4)") (class "Default")
      (node (ref "IC18") (pin "4") (pinfunction "C2B_4") (pintype "output+no_connect"))
    )
    (net (code "118") (name "unconnected-(IC18-CKOUT1+-Pad28)") (class "Default")
      (node (ref "IC18") (pin "28") (pinfunction "CKOUT1+_28") (pintype "output+no_connect"))
    )
    (net (code "119") (name "unconnected-(IC18-CKOUT1--Pad29)") (class "Default")
      (node (ref "IC18") (pin "29") (pinfunction "CKOUT1-_29") (pintype "output+no_connect"))
    )
    (net (code "120") (name "unconnected-(IC18-LOL-Pad18)") (class "Default")
      (node (ref "IC18") (pin "18") (pinfunction "LOL_18") (pintype "output+no_connect"))
    )
    (net (code "121") (name "unconnected-(IC18-NC-Pad2)") (class "Default")
      (node (ref "IC18") (pin "2") (pinfunction "NC_2") (pintype "passive+no_connect"))
    )
    (net (code "122") (name "unconnected-(IC18-NC-Pad9)") (class "Default")
      (node (ref "IC18") (pin "9") (pinfunction "NC_9") (pintype "passive+no_connect"))
    )
    (net (code "123") (name "unconnected-(IC18-NC-Pad14)") (class "Default")
      (node (ref "IC18") (pin "14") (pinfunction "NC_14") (pintype "passive+no_connect"))
    )
    (net (code "124") (name "unconnected-(IC18-NC-Pad30)") (class "Default")
      (node (ref "IC18") (pin "30") (pinfunction "NC_30") (pintype "passive+no_connect"))
    )
    (net (code "125") (name "unconnected-(IC18-NC-Pad33)") (class "Default")
      (node (ref "IC18") (pin "33") (pinfunction "NC_33") (pintype "passive+no_connect"))
    )
    (net (code "126") (name "unconnected-(IC18-RATE0-Pad11)") (class "Default")
      (node (ref "IC18") (pin "11") (pinfunction "RATE0_11") (pintype "input+no_connect"))
    )
    (net (code "127") (name "unconnected-(IC18-RATE1-Pad15)") (class "Default")
      (node (ref "IC18") (pin "15") (pinfunction "RATE1_15") (pintype "input+no_connect"))
    )
    (net (code "128") (name "unconnected-(IC18-SDI-Pad27)") (class "Default")
      (node (ref "IC18") (pin "27") (pinfunction "SDI_27") (pintype "input+no_connect"))
    )
  )
)
